# tritag.net
KiCad netlist of a schematic drawn in EAGLE
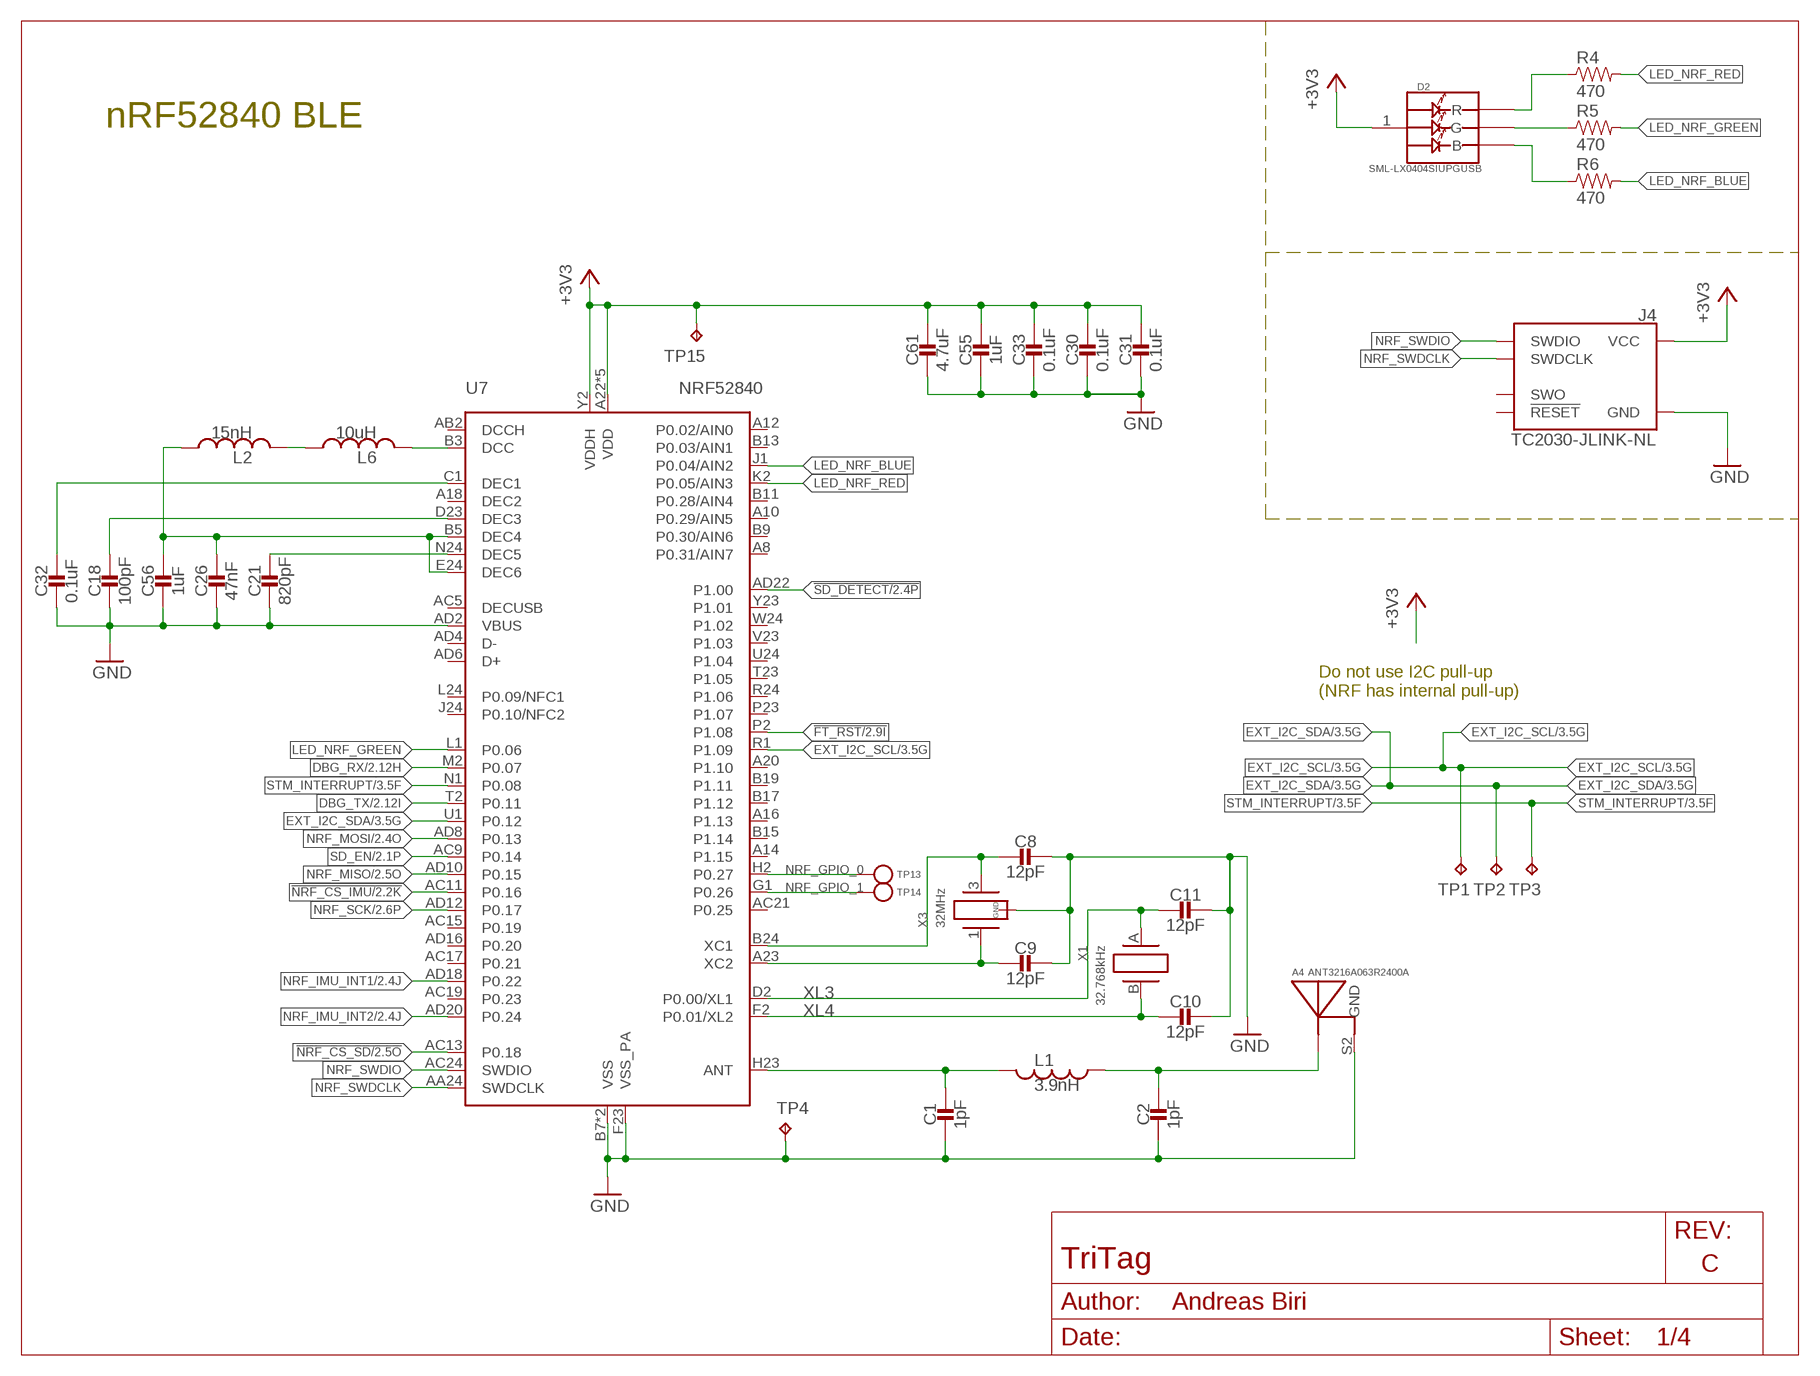
[diagram p0: schematic, sheet 1]
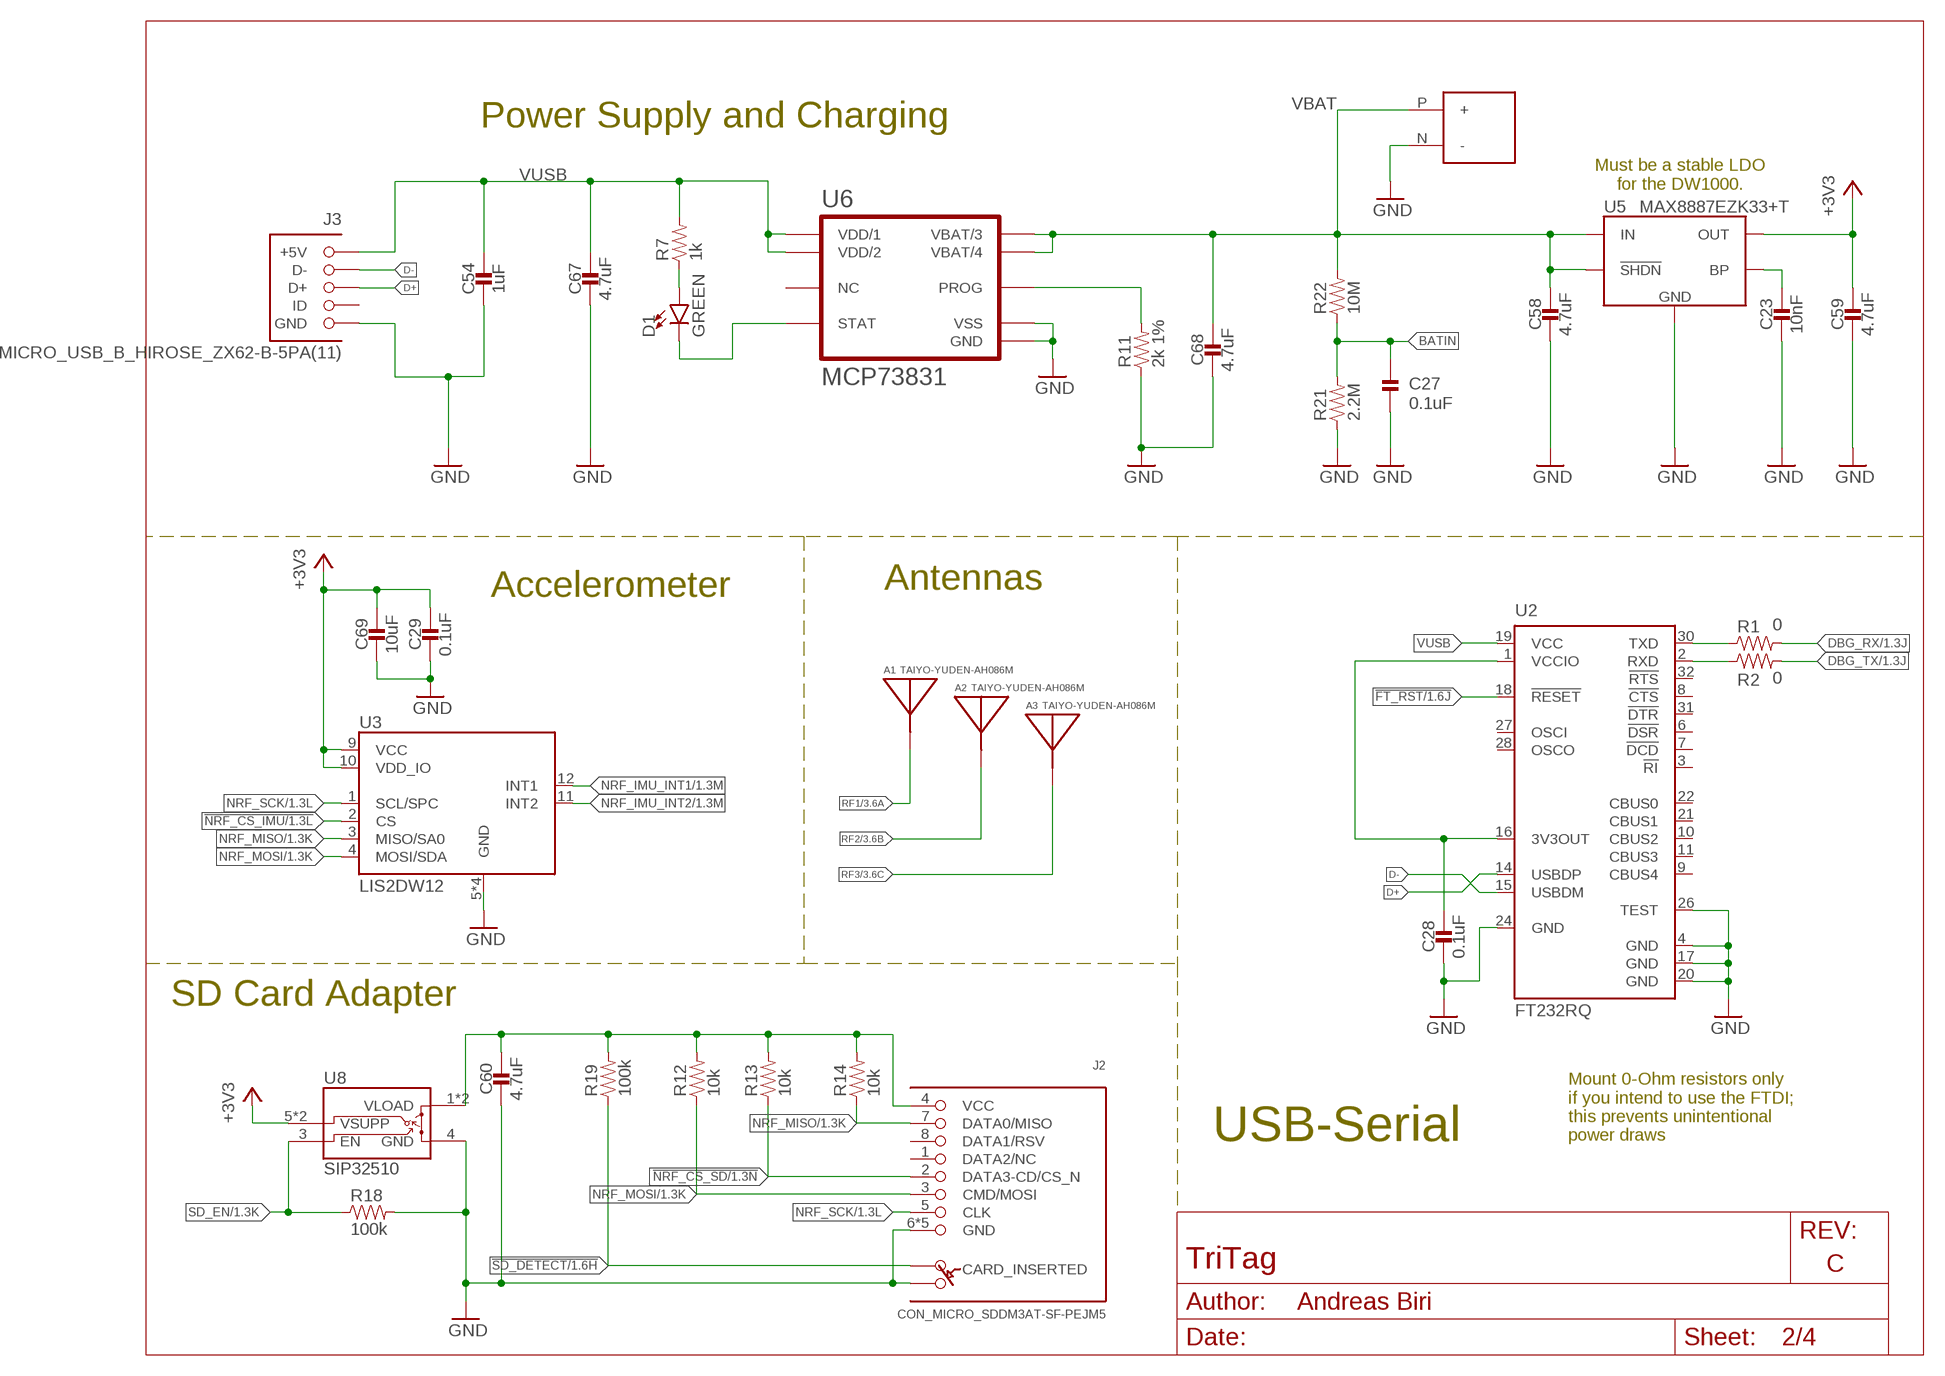
[diagram p1: schematic, sheet 2]
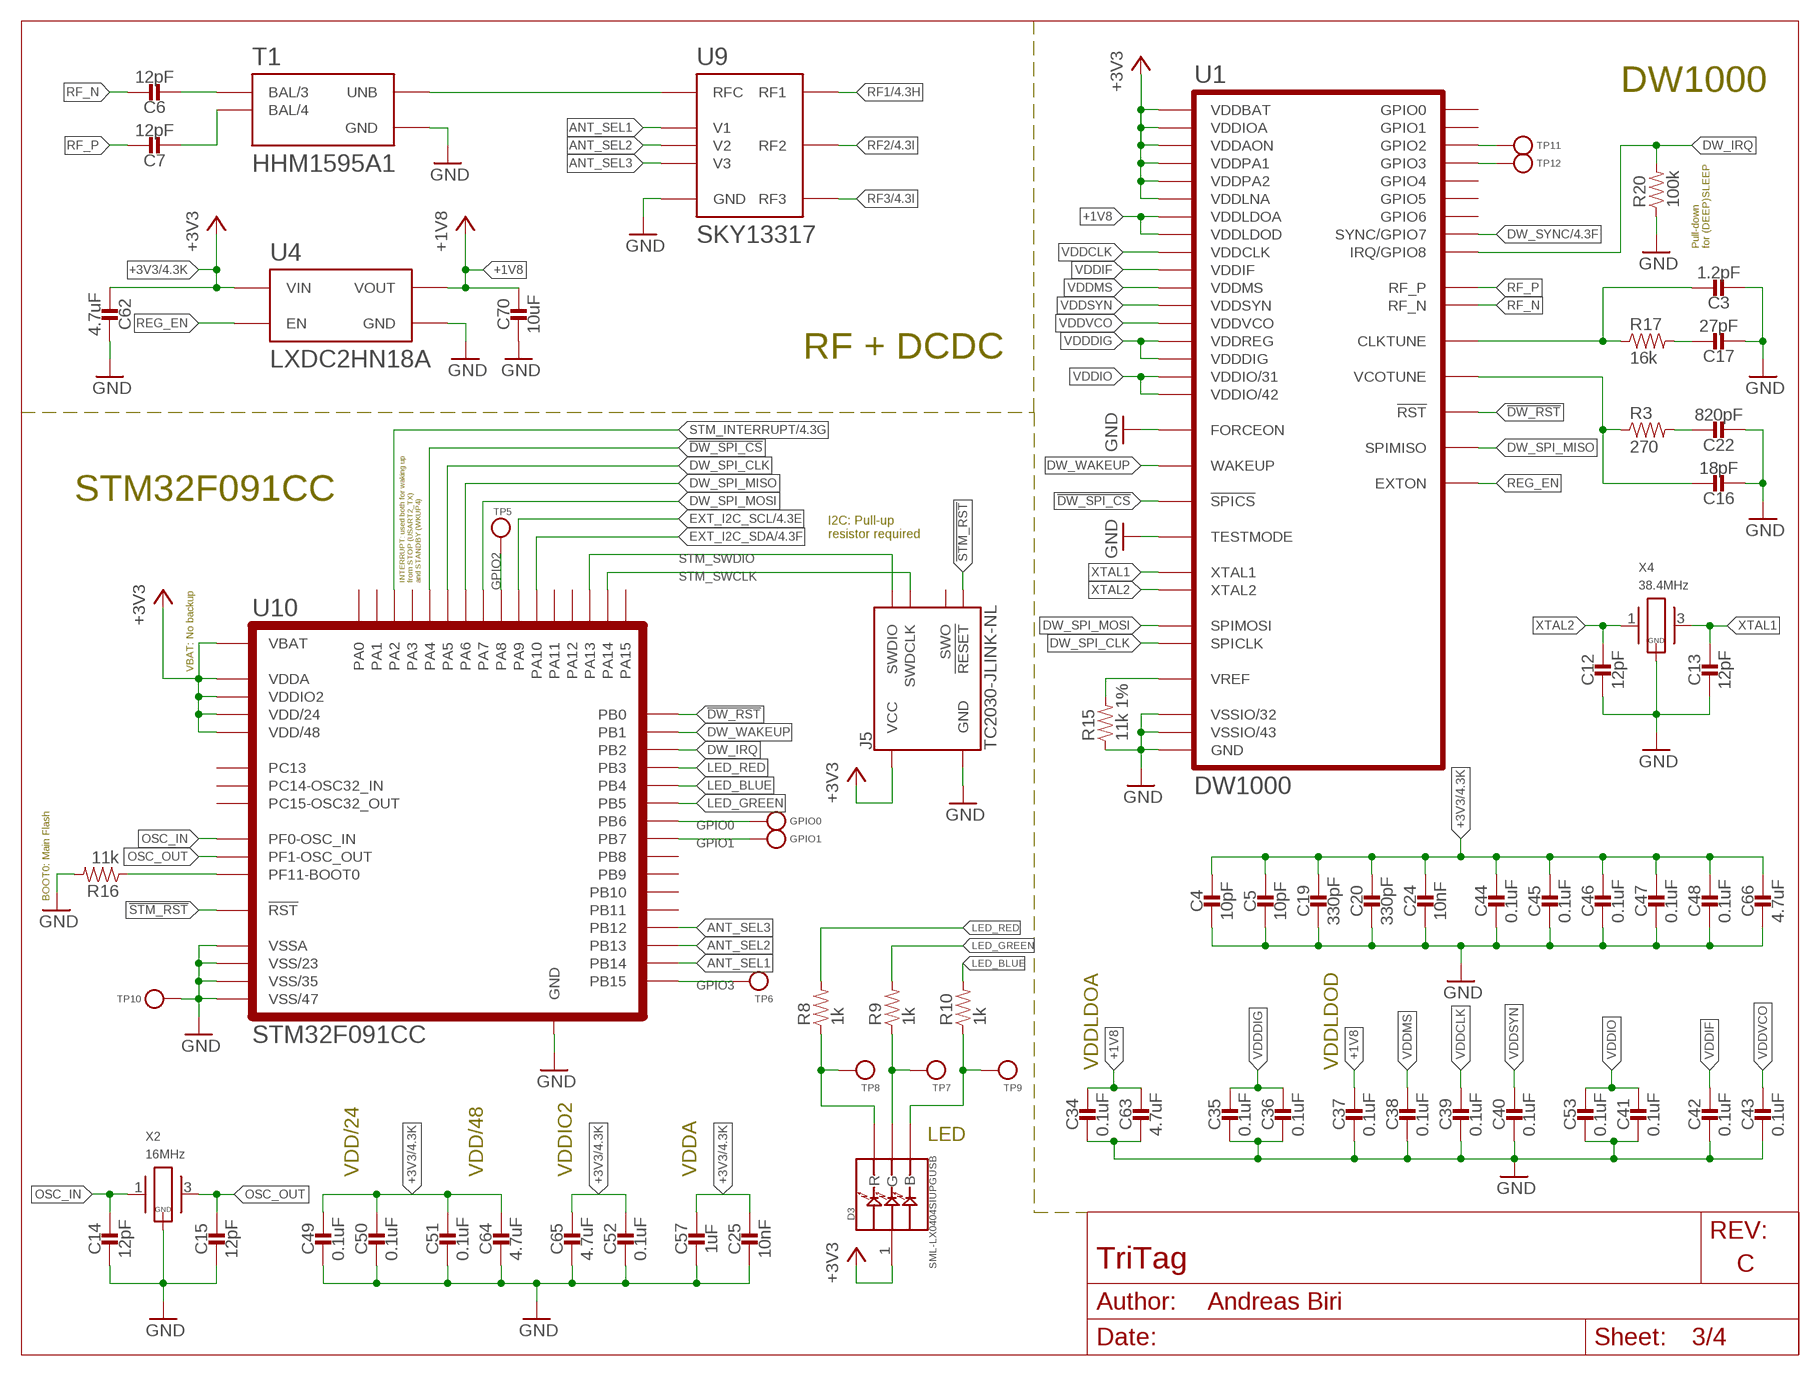
[diagram p2: schematic, sheet 3]
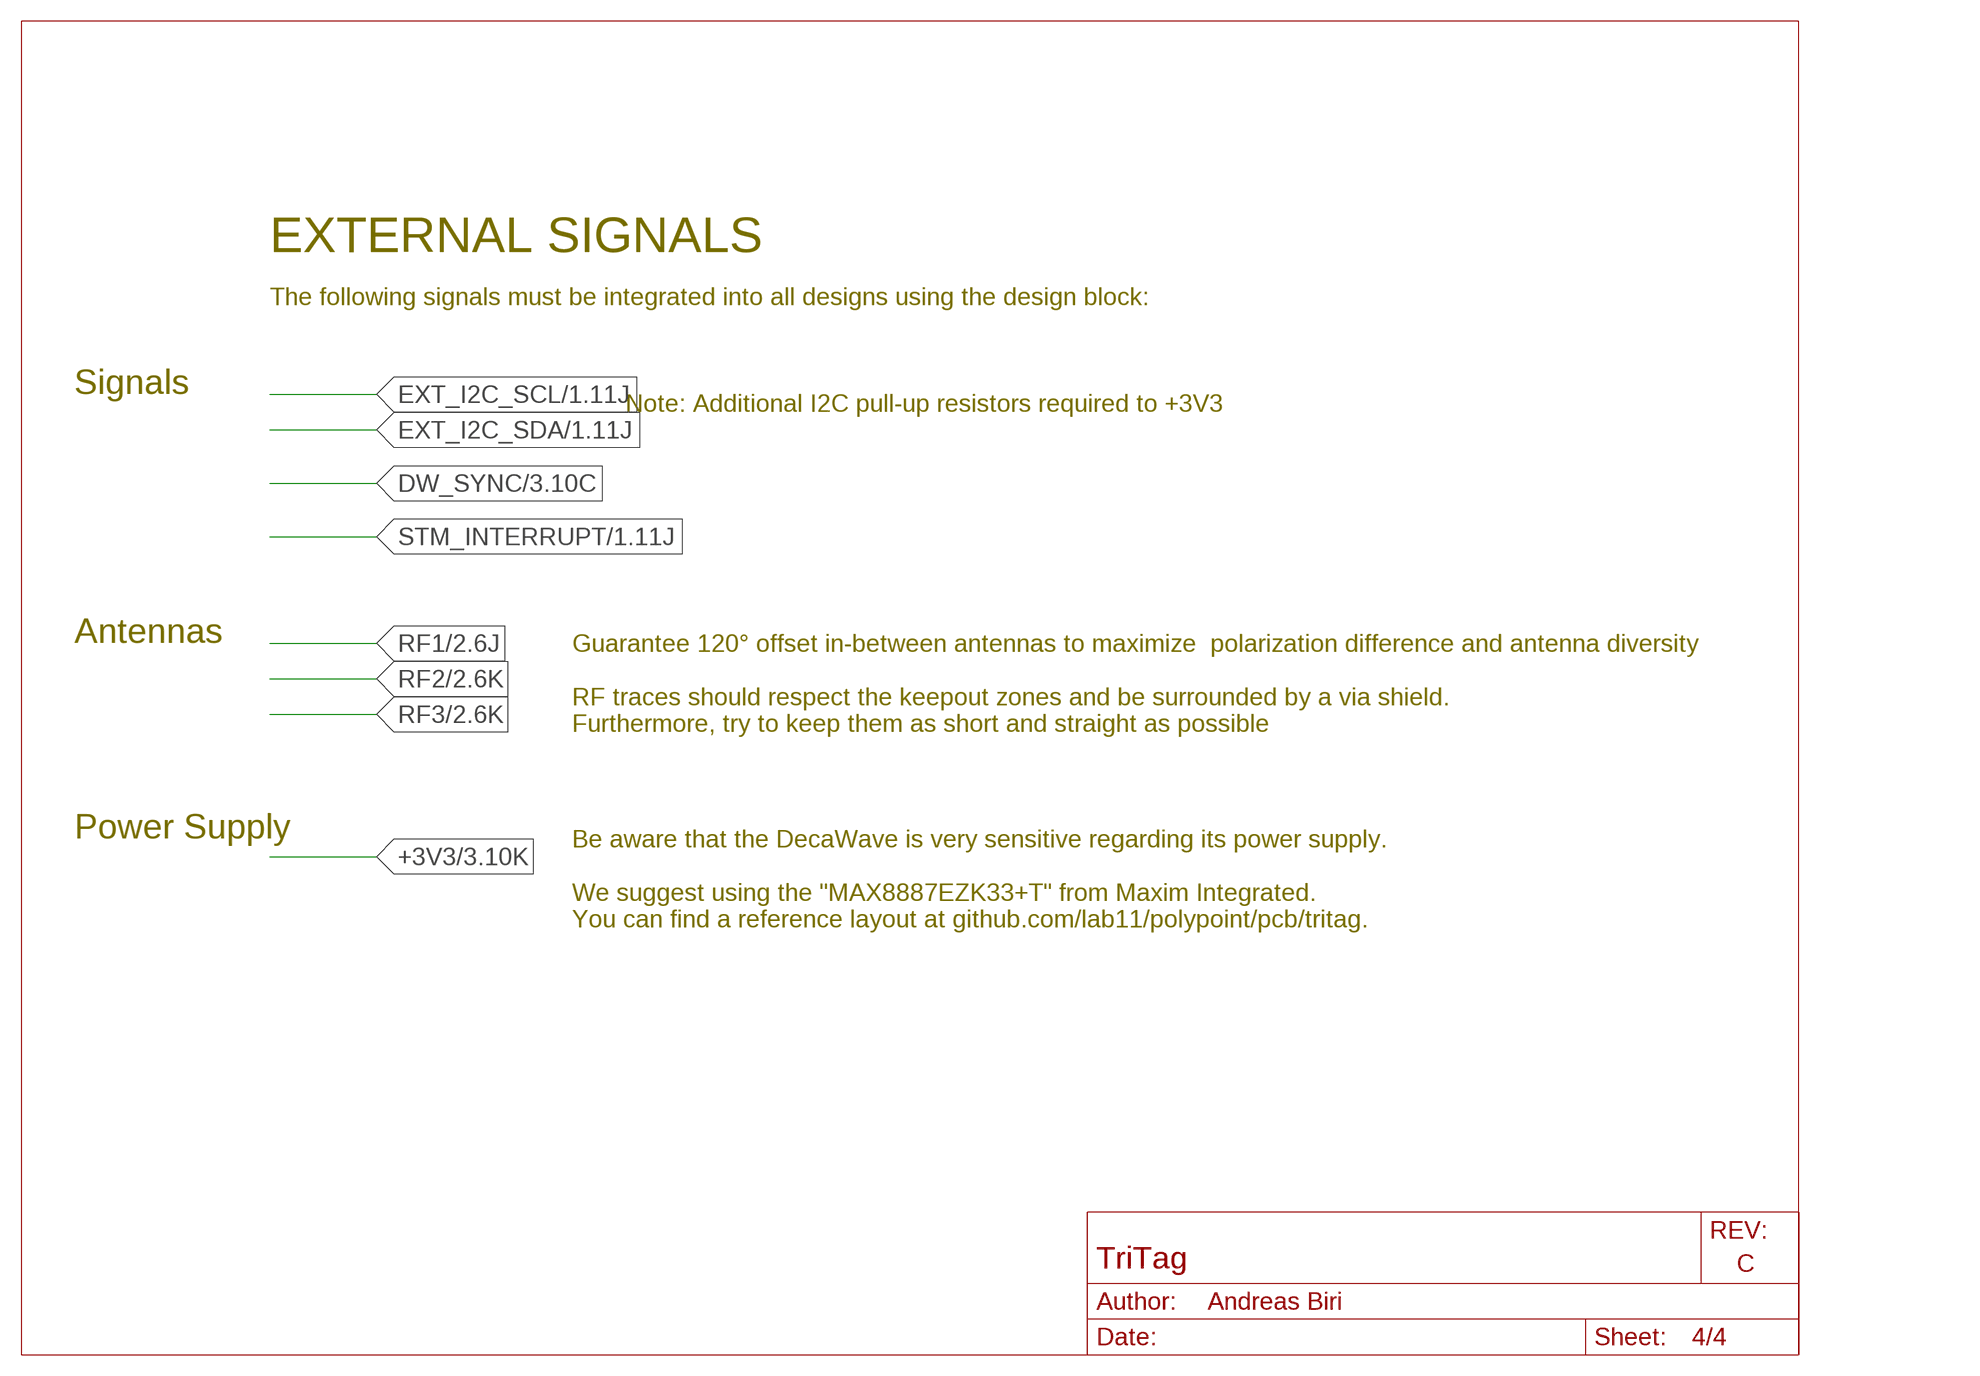
[diagram p3: schematic, sheet 4]

(export (version "E")
  (design (tool "Eeschema 10.0.6"))
  (components
    (comp (ref "A4")
      (value "ANT3216A063R2400A")
      (footprint "eagle-import:ANT3216A063R2400A")
      (fields (field (name "MANUFACTURER") "YAGEO"))
      (libsource (lib "eagle-import") (part "ANT3216A063R2400A"))
    )
    (comp (ref "C1")
      (value "1pF")
      (footprint "eagle-import:0402_CAP")
      (fields (field (name "MPN") "GJM1555C1H1R0CB01D "))
      (libsource (lib "eagle-import") (part "CAPACITOR0402_CAP"))
    )
    (comp (ref "C2")
      (value "1pF")
      (footprint "eagle-import:0402_CAP")
      (fields (field (name "MPN") "GJM1555C1H1R0CB01D"))
      (libsource (lib "eagle-import") (part "CAPACITOR0402_CAP"))
    )
    (comp (ref "C8")
      (value "12pF")
      (footprint "eagle-import:0402_CAP")
      (fields (field (name "MPN") "GRM1555C1H120GA01D "))
      (libsource (lib "eagle-import") (part "CAPACITOR0402_CAP"))
    )
    (comp (ref "C9")
      (value "12pF")
      (footprint "eagle-import:0402_CAP")
      (fields (field (name "MPN") "GRM1555C1H120GA01D "))
      (libsource (lib "eagle-import") (part "CAPACITOR0402_CAP"))
    )
    (comp (ref "C10")
      (value "12pF")
      (footprint "eagle-import:0402_CAP")
      (fields (field (name "MPN") "GRM1555C1H120GA01D "))
      (libsource (lib "eagle-import") (part "CAPACITOR0402_CAP"))
    )
    (comp (ref "C11")
      (value "12pF")
      (footprint "eagle-import:0402_CAP")
      (fields (field (name "MPN") "GRM1555C1H120GA01D "))
      (libsource (lib "eagle-import") (part "CAPACITOR0402_CAP"))
    )
    (comp (ref "C18")
      (value "100pF")
      (footprint "eagle-import:0402_CAP")
      (fields (field (name "MPN") "GRM1555C1H101JA01D "))
      (libsource (lib "eagle-import") (part "CAPACITOR0402_CAP"))
    )
    (comp (ref "C21")
      (value "820pF")
      (footprint "eagle-import:0402_CAP")
      (fields (field (name "MPN") "CL05C821JB5NFNC"))
      (libsource (lib "eagle-import") (part "CAPACITOR0402_CAP"))
    )
    (comp (ref "C26")
      (value "47nF")
      (footprint "eagle-import:0402_CAP")
      (fields (field (name "MPN") "C1005X7R1C473K050BC "))
      (libsource (lib "eagle-import") (part "CAPACITOR0402_CAP"))
    )
    (comp (ref "C30")
      (value "0.1uF")
      (footprint "eagle-import:0402_CAP")
      (fields (field (name "MPN") "GRM155R71C104KA88J "))
      (libsource (lib "eagle-import") (part "CAPACITOR0402_CAP"))
    )
    (comp (ref "C31")
      (value "0.1uF")
      (footprint "eagle-import:0402_CAP")
      (fields (field (name "MPN") "GRM155R71C104KA88J "))
      (libsource (lib "eagle-import") (part "CAPACITOR0402_CAP"))
    )
    (comp (ref "C32")
      (value "0.1uF")
      (footprint "eagle-import:0402_CAP")
      (fields (field (name "MPN") "GRM155R71C104KA88J "))
      (libsource (lib "eagle-import") (part "CAPACITOR0402_CAP"))
    )
    (comp (ref "C33")
      (value "0.1uF")
      (footprint "eagle-import:0402_CAP")
      (fields (field (name "MPN") "GRM155R71C104KA88J "))
      (libsource (lib "eagle-import") (part "CAPACITOR0402_CAP"))
    )
    (comp (ref "C55")
      (value "1uF")
      (footprint "eagle-import:0402_CAP")
      (fields (field (name "MPN") "GRM155R70G105KA12D "))
      (libsource (lib "eagle-import") (part "CAPACITOR0402_CAP"))
    )
    (comp (ref "C56")
      (value "1uF")
      (footprint "eagle-import:0402_CAP")
      (fields (field (name "MPN") "GRM155R70G105KA12D "))
      (libsource (lib "eagle-import") (part "CAPACITOR0402_CAP"))
    )
    (comp (ref "C61")
      (value "4.7uF")
      (footprint "eagle-import:0402_CAP")
      (fields (field (name "MPN") "C1005X5R0J475K050BC "))
      (libsource (lib "eagle-import") (part "CAPACITOR0402_CAP"))
    )
    (comp (ref "D2")
      (value "SML-LX0404SIUPGUSB")
      (footprint "eagle-import:1MM_SQ_4PAD")
      (fields (field (name "MANUFACTURER") "Lumex Opto"))
      (libsource (lib "eagle-import") (part "SML-LX0404SIUPGUSB"))
    )
    (comp (ref "J4")
      (value "TC2030-JLINK-NL")
      (footprint "eagle-import:TC2030-IDC-NL")
      (libsource (lib "eagle-import") (part "TC2030-JLINK-NL"))
    )
    (comp (ref "L1")
      (value "3.9nH")
      (footprint "eagle-import:0402_CAP")
      (fields (field (name "MPN") "AISC-0402-3N9G-T "))
      (libsource (lib "eagle-import") (part "INDUCTOR0402"))
    )
    (comp (ref "L2")
      (value "15nH")
      (footprint "eagle-import:0402_CAP")
      (fields (field (name "MPN") "HK100515NJ-T "))
      (libsource (lib "eagle-import") (part "INDUCTOR0402"))
    )
    (comp (ref "L6")
      (value "10uH")
      (footprint "eagle-import:0603_CAP")
      (fields (field (name "MPN") "LQM18FN100M00D "))
      (libsource (lib "eagle-import") (part "INDUCTOR0603"))
    )
    (comp (ref "R4")
      (value "470")
      (footprint "eagle-import:0402_RES")
      (libsource (lib "eagle-import") (part "RESISTOR0402_RES"))
    )
    (comp (ref "R5")
      (value "470")
      (footprint "eagle-import:0402_RES")
      (libsource (lib "eagle-import") (part "RESISTOR0402_RES"))
    )
    (comp (ref "R6")
      (value "470")
      (footprint "eagle-import:0402_RES")
      (libsource (lib "eagle-import") (part "RESISTOR0402_RES"))
    )
    (comp (ref "TP1")
      (value "TPTP06SQ")
      (footprint "eagle-import:TP06SQ")
      (libsource (lib "eagle-import") (part "TPTP06SQ"))
    )
    (comp (ref "TP2")
      (value "TPTP06SQ")
      (footprint "eagle-import:TP06SQ")
      (libsource (lib "eagle-import") (part "TPTP06SQ"))
    )
    (comp (ref "TP3")
      (value "TPTP06SQ")
      (footprint "eagle-import:TP06SQ")
      (libsource (lib "eagle-import") (part "TPTP06SQ"))
    )
    (comp (ref "TP4")
      (value "TPTP06SQ")
      (footprint "eagle-import:TP06SQ")
      (libsource (lib "eagle-import") (part "TPTP06SQ"))
    )
    (comp (ref "TP13")
      (value "TEST-POINT")
      (footprint "eagle-import:PAD.03X.03")
      (libsource (lib "eagle-import") (part "TEST-POINT"))
    )
    (comp (ref "TP14")
      (value "TEST-POINT")
      (footprint "eagle-import:PAD.03X.03")
      (libsource (lib "eagle-import") (part "TEST-POINT"))
    )
    (comp (ref "TP15")
      (value "TPTP06SQ")
      (footprint "eagle-import:TP06SQ")
      (libsource (lib "eagle-import") (part "TPTP06SQ"))
    )
    (comp (ref "U7")
      (value "NRF52840")
      (footprint "eagle-import:AQFN73")
      (fields (field (name "MANUFACTURER") "NORIDIC SEMICONDUCTOR"))
      (libsource (lib "eagle-import") (part "NRF52840"))
    )
    (comp (ref "X1")
      (value "32.768kHz")
      (footprint "eagle-import:ABS05")
      (fields (field (name "MANUFACTURER") "Abracon") (field (name "MPN") "ABS05-32.768KHZ-9-T"))
      (libsource (lib "eagle-import") (part "ABS05-32.768KHZ-9-T"))
    )
    (comp (ref "X3")
      (value "32MHz")
      (footprint "eagle-import:TXC-7V")
      (fields (field (name "MANUFACTURER") "TXC CORPORATION") (field (name "MPN") "7M-32.000MAHV-T"))
      (libsource (lib "eagle-import") (part "7V-32.000MAHV-T"))
    )
    (comp (ref "C3")
      (value "1.2pF")
      (footprint "eagle-import:0402_CAP")
      (libsource (lib "eagle-import") (part "CAPACITOR0402_CAP"))
    )
    (comp (ref "C4")
      (value "10pF")
      (footprint "eagle-import:0402_CAP")
      (libsource (lib "eagle-import") (part "CAPACITOR0402_CAP"))
    )
    (comp (ref "C5")
      (value "10pF")
      (footprint "eagle-import:0402_CAP")
      (libsource (lib "eagle-import") (part "CAPACITOR0402_CAP"))
    )
    (comp (ref "C6")
      (value "12pF")
      (footprint "eagle-import:0201_CAP")
      (libsource (lib "eagle-import") (part "CAPACITOR0201_CAP"))
    )
    (comp (ref "C7")
      (value "12pF")
      (footprint "eagle-import:0201_CAP")
      (libsource (lib "eagle-import") (part "CAPACITOR0201_CAP"))
    )
    (comp (ref "C12")
      (value "12pF")
      (footprint "eagle-import:0402_CAP")
      (libsource (lib "eagle-import") (part "CAPACITOR0402_CAP"))
    )
    (comp (ref "C13")
      (value "12pF")
      (footprint "eagle-import:0402_CAP")
      (libsource (lib "eagle-import") (part "CAPACITOR0402_CAP"))
    )
    (comp (ref "C14")
      (value "12pF")
      (footprint "eagle-import:0402_CAP")
      (libsource (lib "eagle-import") (part "CAPACITOR0402_CAP"))
    )
    (comp (ref "C15")
      (value "12pF")
      (footprint "eagle-import:0402_CAP")
      (libsource (lib "eagle-import") (part "CAPACITOR0402_CAP"))
    )
    (comp (ref "C16")
      (value "18pF")
      (footprint "eagle-import:0402_CAP")
      (libsource (lib "eagle-import") (part "CAPACITOR0402_CAP"))
    )
    (comp (ref "C17")
      (value "27pF")
      (footprint "eagle-import:0402_CAP")
      (libsource (lib "eagle-import") (part "CAPACITOR0402_CAP"))
    )
    (comp (ref "C19")
      (value "330pF")
      (footprint "eagle-import:0402_CAP")
      (libsource (lib "eagle-import") (part "CAPACITOR0402_CAP"))
    )
    (comp (ref "C20")
      (value "330pF")
      (footprint "eagle-import:0402_CAP")
      (libsource (lib "eagle-import") (part "CAPACITOR0402_CAP"))
    )
    (comp (ref "C22")
      (value "820pF")
      (footprint "eagle-import:0402_CAP")
      (libsource (lib "eagle-import") (part "CAPACITOR0402_CAP"))
    )
    (comp (ref "C24")
      (value "10nF")
      (footprint "eagle-import:0402_CAP")
      (libsource (lib "eagle-import") (part "CAPACITOR0402_CAP"))
    )
    (comp (ref "C25")
      (value "10nF")
      (footprint "eagle-import:0402_CAP")
      (libsource (lib "eagle-import") (part "CAPACITOR0402_CAP"))
    )
    (comp (ref "C34")
      (value "0.1uF")
      (footprint "eagle-import:0402_CAP")
      (libsource (lib "eagle-import") (part "CAPACITOR0402_CAP"))
    )
    (comp (ref "C35")
      (value "0.1uF")
      (footprint "eagle-import:0402_CAP")
      (libsource (lib "eagle-import") (part "CAPACITOR0402_CAP"))
    )
    (comp (ref "C36")
      (value "0.1uF")
      (footprint "eagle-import:0402_CAP")
      (libsource (lib "eagle-import") (part "CAPACITOR0402_CAP"))
    )
    (comp (ref "C37")
      (value "0.1uF")
      (footprint "eagle-import:0402_CAP")
      (libsource (lib "eagle-import") (part "CAPACITOR0402_CAP"))
    )
    (comp (ref "C38")
      (value "0.1uF")
      (footprint "eagle-import:0402_CAP")
      (libsource (lib "eagle-import") (part "CAPACITOR0402_CAP"))
    )
    (comp (ref "C39")
      (value "0.1uF")
      (footprint "eagle-import:0402_CAP")
      (libsource (lib "eagle-import") (part "CAPACITOR0402_CAP"))
    )
    (comp (ref "C40")
      (value "0.1uF")
      (footprint "eagle-import:0402_CAP")
      (libsource (lib "eagle-import") (part "CAPACITOR0402_CAP"))
    )
    (comp (ref "C41")
      (value "0.1uF")
      (footprint "eagle-import:0402_CAP")
      (libsource (lib "eagle-import") (part "CAPACITOR0402_CAP"))
    )
    (comp (ref "C42")
      (value "0.1uF")
      (footprint "eagle-import:0402_CAP")
      (libsource (lib "eagle-import") (part "CAPACITOR0402_CAP"))
    )
    (comp (ref "C43")
      (value "0.1uF")
      (footprint "eagle-import:0402_CAP")
      (libsource (lib "eagle-import") (part "CAPACITOR0402_CAP"))
    )
    (comp (ref "C44")
      (value "0.1uF")
      (footprint "eagle-import:0402_CAP")
      (libsource (lib "eagle-import") (part "CAPACITOR0402_CAP"))
    )
    (comp (ref "C45")
      (value "0.1uF")
      (footprint "eagle-import:0402_CAP")
      (libsource (lib "eagle-import") (part "CAPACITOR0402_CAP"))
    )
    (comp (ref "C46")
      (value "0.1uF")
      (footprint "eagle-import:0402_CAP")
      (libsource (lib "eagle-import") (part "CAPACITOR0402_CAP"))
    )
    (comp (ref "C47")
      (value "0.1uF")
      (footprint "eagle-import:0402_CAP")
      (libsource (lib "eagle-import") (part "CAPACITOR0402_CAP"))
    )
    (comp (ref "C48")
      (value "0.1uF")
      (footprint "eagle-import:0402_CAP")
      (libsource (lib "eagle-import") (part "CAPACITOR0402_CAP"))
    )
    (comp (ref "C49")
      (value "0.1uF")
      (footprint "eagle-import:0402_CAP")
      (libsource (lib "eagle-import") (part "CAPACITOR0402_CAP"))
    )
    (comp (ref "C50")
      (value "0.1uF")
      (footprint "eagle-import:0402_CAP")
      (libsource (lib "eagle-import") (part "CAPACITOR0402_CAP"))
    )
    (comp (ref "C51")
      (value "0.1uF")
      (footprint "eagle-import:0402_CAP")
      (libsource (lib "eagle-import") (part "CAPACITOR0402_CAP"))
    )
    (comp (ref "C52")
      (value "0.1uF")
      (footprint "eagle-import:0402_CAP")
      (libsource (lib "eagle-import") (part "CAPACITOR0402_CAP"))
    )
    (comp (ref "C53")
      (value "0.1uF")
      (footprint "eagle-import:0402_CAP")
      (libsource (lib "eagle-import") (part "CAPACITOR0402_CAP"))
    )
    (comp (ref "C57")
      (value "1uF")
      (footprint "eagle-import:0402_CAP")
      (libsource (lib "eagle-import") (part "CAPACITOR0402_CAP"))
    )
    (comp (ref "C62")
      (value "4.7uF")
      (footprint "eagle-import:0402_CAP")
      (libsource (lib "eagle-import") (part "CAPACITOR0402_CAP"))
    )
    (comp (ref "C63")
      (value "4.7uF")
      (footprint "eagle-import:0402_CAP")
      (libsource (lib "eagle-import") (part "CAPACITOR0402_CAP"))
    )
    (comp (ref "C64")
      (value "4.7uF")
      (footprint "eagle-import:0402_CAP")
      (libsource (lib "eagle-import") (part "CAPACITOR0402_CAP"))
    )
    (comp (ref "C65")
      (value "4.7uF")
      (footprint "eagle-import:0402_CAP")
      (libsource (lib "eagle-import") (part "CAPACITOR0402_CAP"))
    )
    (comp (ref "C66")
      (value "4.7uF")
      (footprint "eagle-import:0402_CAP")
      (libsource (lib "eagle-import") (part "CAPACITOR0402_CAP"))
    )
    (comp (ref "C70")
      (value "10uF")
      (footprint "eagle-import:0603_CAP")
      (libsource (lib "eagle-import") (part "CAPACITOR0603_CAP"))
    )
    (comp (ref "D3")
      (value "SML-LX0404SIUPGUSB")
      (footprint "eagle-import:1MM_SQ_4PAD")
      (fields (field (name "MANUFACTURER") "Lumex Opto"))
      (libsource (lib "eagle-import") (part "SML-LX0404SIUPGUSB"))
    )
    (comp (ref "GPIO0")
      (value "TEST-POINT")
      (footprint "eagle-import:PAD.03X.03")
      (libsource (lib "eagle-import") (part "TEST-POINT"))
    )
    (comp (ref "GPIO1")
      (value "TEST-POINT")
      (footprint "eagle-import:PAD.03X.03")
      (libsource (lib "eagle-import") (part "TEST-POINT"))
    )
    (comp (ref "J5")
      (value "TC2030-JLINK-NL")
      (footprint "eagle-import:TC2030-IDC-NL")
      (libsource (lib "eagle-import") (part "TC2030-JLINK-NL"))
    )
    (comp (ref "R3")
      (value "270")
      (footprint "eagle-import:0402_RES")
      (libsource (lib "eagle-import") (part "RESISTOR0402_RES"))
    )
    (comp (ref "R8")
      (value "1k")
      (footprint "eagle-import:0402_RES")
      (libsource (lib "eagle-import") (part "RESISTOR0402_RES"))
    )
    (comp (ref "R9")
      (value "1k")
      (footprint "eagle-import:0402_RES")
      (libsource (lib "eagle-import") (part "RESISTOR0402_RES"))
    )
    (comp (ref "R10")
      (value "1k")
      (footprint "eagle-import:0402_RES")
      (libsource (lib "eagle-import") (part "RESISTOR0402_RES"))
    )
    (comp (ref "R15")
      (value "11k 1%")
      (footprint "eagle-import:0402_RES")
      (libsource (lib "eagle-import") (part "RESISTOR0402_RES"))
    )
    (comp (ref "R16")
      (value "11k")
      (footprint "eagle-import:0402_RES")
      (libsource (lib "eagle-import") (part "RESISTOR0402_RES"))
    )
    (comp (ref "R17")
      (value "16k")
      (footprint "eagle-import:0402_RES")
      (libsource (lib "eagle-import") (part "RESISTOR0402_RES"))
    )
    (comp (ref "R20")
      (value "100k")
      (footprint "eagle-import:0402_RES")
      (libsource (lib "eagle-import") (part "RESISTOR0402_RES"))
    )
    (comp (ref "T1")
      (value "HHM1595A1")
      (footprint "eagle-import:EIA-0805")
      (fields (field (name "MANUFACTURER") "TDK Corporation"))
      (libsource (lib "eagle-import") (part "HHM1595A1"))
    )
    (comp (ref "TP5")
      (value "TEST-POINT")
      (footprint "eagle-import:PAD.03X.03")
      (libsource (lib "eagle-import") (part "TEST-POINT"))
    )
    (comp (ref "TP6")
      (value "TEST-POINT")
      (footprint "eagle-import:PAD.03X.03")
      (libsource (lib "eagle-import") (part "TEST-POINT"))
    )
    (comp (ref "TP7")
      (value "TEST-POINT")
      (footprint "eagle-import:PAD.03X.03")
      (libsource (lib "eagle-import") (part "TEST-POINT"))
    )
    (comp (ref "TP8")
      (value "TEST-POINT")
      (footprint "eagle-import:PAD.03X.03")
      (libsource (lib "eagle-import") (part "TEST-POINT"))
    )
    (comp (ref "TP9")
      (value "TEST-POINT")
      (footprint "eagle-import:PAD.03X.03")
      (libsource (lib "eagle-import") (part "TEST-POINT"))
    )
    (comp (ref "TP10")
      (value "TEST-POINT")
      (footprint "eagle-import:PAD.03X.03")
      (libsource (lib "eagle-import") (part "TEST-POINT"))
    )
    (comp (ref "TP11")
      (value "TEST-POINT")
      (footprint "eagle-import:PAD.03X.03")
      (libsource (lib "eagle-import") (part "TEST-POINT"))
    )
    (comp (ref "TP12")
      (value "TEST-POINT")
      (footprint "eagle-import:PAD.03X.03")
      (libsource (lib "eagle-import") (part "TEST-POINT"))
    )
    (comp (ref "U1")
      (value "DW1000")
      (footprint "eagle-import:QFN-48-DW1000")
      (fields (field (name "MANUFACTURER") "Decawave Limited") (field (name "MPN") "DW1000-I-TR13"))
      (libsource (lib "eagle-import") (part "DW1000"))
    )
    (comp (ref "U4")
      (value "LXDC2HN18A")
      (footprint "eagle-import:LXDC2HN")
      (fields
        (field (name "MANUFACTURER") "Murata Electronics North America")
        (field (name "MPN") "LXDC2HN18A-097")
      )
      (libsource (lib "eagle-import") (part "LXDC2HN18A"))
    )
    (comp (ref "U9")
      (value "SKY13317")
      (footprint "eagle-import:MLPQ-UT-8")
      (fields (field (name "MANUFACTURER") "Skyworks Solutions Inc.") (field (name "MPN") "SKY13317-373LF"))
      (libsource (lib "eagle-import") (part "SKY13317"))
    )
    (comp (ref "U10")
      (value "STM32F091CC")
      (footprint "eagle-import:UFQFPN-48")
      (fields (field (name "MANUFACTURER") "STMicroelectronics") (field (name "MPN") "STM32F091CCU6"))
      (libsource (lib "eagle-import") (part "STM32F091CC"))
    )
    (comp (ref "X2")
      (value "16MHz")
      (footprint "eagle-import:FA-20H")
      (description "16MHz ±10ppm Crystal 8pF 80 Ohms 4-SMD, No Lead")
      (fields (field (name "MANUFACTURER") "EPSON"))
      (libsource (lib "eagle-import") (part "FA-20H"))
    )
    (comp (ref "X4")
      (value "38.4MHz")
      (footprint "eagle-import:FA-20H")
      (description "38.4MHz ±10ppm Crystal 8.5pF 40 Ohms 4-SMD, No Lead")
      (fields (field (name "MANUFACTURER") "EPSON"))
      (libsource (lib "eagle-import") (part "FA-20H"))
    )
    (comp (ref "A1")
      (value "TAIYO-YUDEN-AH086M")
      (footprint "eagle-import:TAIYO-YUDEN-AH086M")
      (libsource (lib "eagle-import") (part "TAIYO-YUDEN-AH086M"))
    )
    (comp (ref "A2")
      (value "TAIYO-YUDEN-AH086M")
      (footprint "eagle-import:TAIYO-YUDEN-AH086M")
      (libsource (lib "eagle-import") (part "TAIYO-YUDEN-AH086M"))
    )
    (comp (ref "A3")
      (value "TAIYO-YUDEN-AH086M")
      (footprint "eagle-import:TAIYO-YUDEN-AH086M")
      (libsource (lib "eagle-import") (part "TAIYO-YUDEN-AH086M"))
    )
    (comp (ref "C23")
      (value "10nF")
      (footprint "eagle-import:0402_CAP")
      (libsource (lib "eagle-import") (part "CAPACITOR0402_CAP"))
    )
    (comp (ref "C27")
      (value "0.1uF")
      (footprint "eagle-import:0402_CAP")
      (libsource (lib "eagle-import") (part "CAPACITOR0402_CAP"))
    )
    (comp (ref "C28")
      (value "0.1uF")
      (footprint "eagle-import:0402_CAP")
      (fields (field (name "MPN") "GRM155R71C104KA88J "))
      (libsource (lib "eagle-import") (part "CAPACITOR0402_CAP"))
    )
    (comp (ref "C29")
      (value "0.1uF")
      (footprint "eagle-import:0402_CAP")
      (fields (field (name "MPN") "GRM155R71C104KA88J "))
      (libsource (lib "eagle-import") (part "CAPACITOR0402_CAP"))
    )
    (comp (ref "C54")
      (value "1uF")
      (footprint "eagle-import:0402_CAP")
      (libsource (lib "eagle-import") (part "CAPACITOR0402_CAP"))
    )
    (comp (ref "C58")
      (value "4.7uF")
      (footprint "eagle-import:0402_CAP")
      (libsource (lib "eagle-import") (part "CAPACITOR0402_CAP"))
    )
    (comp (ref "C59")
      (value "4.7uF")
      (footprint "eagle-import:0402_CAP")
      (libsource (lib "eagle-import") (part "CAPACITOR0402_CAP"))
    )
    (comp (ref "C60")
      (value "4.7uF")
      (footprint "eagle-import:0402_CAP")
      (description "CAP CER 4.7UF 6.3V X5R 0402")
      (fields (field (name "MANUFACTURER") "TDK") (field (name "MPN") "C1005X5R0J475K050BC"))
      (libsource (lib "eagle-import") (part "CAPACITOR0402_CAP"))
    )
    (comp (ref "C67")
      (value "4.7uF")
      (footprint "eagle-import:0402_CAP")
      (libsource (lib "eagle-import") (part "CAPACITOR0402_CAP"))
    )
    (comp (ref "C68")
      (value "4.7uF")
      (footprint "eagle-import:0402_CAP")
      (libsource (lib "eagle-import") (part "CAPACITOR0402_CAP"))
    )
    (comp (ref "C69")
      (value "10uF")
      (footprint "eagle-import:0603_CAP")
      (fields (field (name "MPN") "GRM188R60J106ME47D "))
      (libsource (lib "eagle-import") (part "CAPACITOR0603_CAP"))
    )
    (comp (ref "D1")
      (value "GREEN")
      (footprint "eagle-import:LED-0603")
      (libsource (lib "eagle-import") (part "LED0603"))
    )
    (comp (ref "J1")
      (value "BAT_HOLE")
      (footprint "eagle-import:BATTERY_HOLE")
      (libsource (lib "eagle-import") (part "BAT_HOLE"))
    )
    (comp (ref "J2")
      (value "CON_MICRO_SDDM3AT-SF-PEJM5")
      (footprint "eagle-import:DM3AT-SF-PEJM5")
      (libsource (lib "eagle-import") (part "CON_MICRO_SDDM3AT-SF-PEJM5"))
    )
    (comp (ref "J3")
      (value "MICRO_USB_B_HIROSE_ZX62-B-5PA(11)")
      (footprint "eagle-import:USB_MICRO_B-HIROSE-ZX62-B-5PA(11)")
      (libsource (lib "eagle-import") (part "MICRO_USB_B_HIROSE_ZX62-B-5PA(11)"))
    )
    (comp (ref "R1")
      (value "0")
      (footprint "eagle-import:0402_RES")
      (libsource (lib "eagle-import") (part "RESISTOR0402_RES"))
    )
    (comp (ref "R2")
      (value "0")
      (footprint "eagle-import:0402_RES")
      (libsource (lib "eagle-import") (part "RESISTOR0402_RES"))
    )
    (comp (ref "R7")
      (value "1k")
      (footprint "eagle-import:0402_RES")
      (libsource (lib "eagle-import") (part "RESISTOR0402_RES"))
    )
    (comp (ref "R11")
      (value "2k 1%")
      (footprint "eagle-import:0402_RES")
      (libsource (lib "eagle-import") (part "RESISTOR0402_RES"))
    )
    (comp (ref "R12")
      (value "10k")
      (footprint "eagle-import:0402_RES")
      (libsource (lib "eagle-import") (part "RESISTOR0402_RES"))
    )
    (comp (ref "R13")
      (value "10k")
      (footprint "eagle-import:0402_RES")
      (libsource (lib "eagle-import") (part "RESISTOR0402_RES"))
    )
    (comp (ref "R14")
      (value "10k")
      (footprint "eagle-import:0402_RES")
      (libsource (lib "eagle-import") (part "RESISTOR0402_RES"))
    )
    (comp (ref "R18")
      (value "100k")
      (footprint "eagle-import:0402_RES")
      (libsource (lib "eagle-import") (part "RESISTOR0402_RES"))
    )
    (comp (ref "R19")
      (value "100k")
      (footprint "eagle-import:0402_RES")
      (libsource (lib "eagle-import") (part "RESISTOR0402_RES"))
    )
    (comp (ref "R21")
      (value "2.2M")
      (footprint "eagle-import:0402_RES")
      (libsource (lib "eagle-import") (part "RESISTOR0402_RES"))
    )
    (comp (ref "R22")
      (value "10M")
      (footprint "eagle-import:0402_RES")
      (libsource (lib "eagle-import") (part "RESISTOR0402_RES"))
    )
    (comp (ref "U2")
      (value "FT232RQ")
      (footprint "eagle-import:QFN32")
      (libsource (lib "eagle-import") (part "FT232RQ"))
    )
    (comp (ref "U3")
      (value "LIS2DW12")
      (footprint "eagle-import:LGA-12")
      (fields (field (name "MANUFACTURER") "STMicroelectronics") (field (name "MPN") "LIS2DW12TR"))
      (libsource (lib "eagle-import") (part "LIS2DW12"))
    )
    (comp (ref "U5")
      (value "MAX8887EZK33+T")
      (footprint "eagle-import:SOT-23-5")
      (libsource (lib "eagle-import") (part "MAX8887EZK33+T"))
    )
    (comp (ref "U6")
      (value "MCP73831")
      (footprint "eagle-import:DFN-8-MCP")
      (fields (field (name "MANUFACTURER") "Microchip Technology") (field (name "MPN") "MCP73831T-2ACI/MC"))
      (libsource (lib "eagle-import") (part "MCP73831"))
    )
    (comp (ref "U8")
      (value "SIP32510")
      (footprint "eagle-import:TSOT23-6")
      (fields (field (name "MANUFACTURER") "Vishay") (field (name "MPN") "SIP32510DT-T1-GE3"))
      (libsource (lib "eagle-import") (part "SIP32510"))
    )
  )
  (nets
    (net (code "1") (name "+1V8") (class "Default")
      (node (ref "C34") (pin "1") (pinfunction "1_1") (pintype "bidirectional"))
      (node (ref "C37") (pin "1") (pinfunction "1_1") (pintype "bidirectional"))
      (node (ref "C63") (pin "1") (pinfunction "1_1") (pintype "bidirectional"))
      (node (ref "C70") (pin "1") (pinfunction "1_1") (pintype "bidirectional"))
      (node (ref "U1") (pin "26") (pinfunction "VDDLDOD_26") (pintype "power_in"))
      (node (ref "U1") (pin "48") (pinfunction "VDDLDOA_48") (pintype "power_in"))
      (node (ref "U4") (pin "3") (pinfunction "VOUT_3") (pintype "power_in"))
    )
    (net (code "2") (name "+3V3") (class "Default")
      (node (ref "C19") (pin "1") (pinfunction "1_1") (pintype "bidirectional"))
      (node (ref "C20") (pin "1") (pinfunction "1_1") (pintype "bidirectional"))
      (node (ref "C24") (pin "1") (pinfunction "1_1") (pintype "bidirectional"))
      (node (ref "C25") (pin "1") (pinfunction "1_1") (pintype "bidirectional"))
      (node (ref "C29") (pin "1") (pinfunction "1_1") (pintype "bidirectional"))
      (node (ref "C30") (pin "1") (pinfunction "1_1") (pintype "bidirectional"))
      (node (ref "C31") (pin "1") (pinfunction "1_1") (pintype "bidirectional"))
      (node (ref "C33") (pin "1") (pinfunction "1_1") (pintype "bidirectional"))
      (node (ref "C4") (pin "1") (pinfunction "1_1") (pintype "bidirectional"))
      (node (ref "C44") (pin "1") (pinfunction "1_1") (pintype "bidirectional"))
      (node (ref "C45") (pin "1") (pinfunction "1_1") (pintype "bidirectional"))
      (node (ref "C46") (pin "1") (pinfunction "1_1") (pintype "bidirectional"))
      (node (ref "C47") (pin "1") (pinfunction "1_1") (pintype "bidirectional"))
      (node (ref "C48") (pin "1") (pinfunction "1_1") (pintype "bidirectional"))
      (node (ref "C49") (pin "1") (pinfunction "1_1") (pintype "bidirectional"))
      (node (ref "C5") (pin "1") (pinfunction "1_1") (pintype "bidirectional"))
      (node (ref "C50") (pin "1") (pinfunction "1_1") (pintype "bidirectional"))
      (node (ref "C51") (pin "1") (pinfunction "1_1") (pintype "bidirectional"))
      (node (ref "C52") (pin "1") (pinfunction "1_1") (pintype "bidirectional"))
      (node (ref "C55") (pin "1") (pinfunction "1_1") (pintype "bidirectional"))
      (node (ref "C57") (pin "1") (pinfunction "1_1") (pintype "bidirectional"))
      (node (ref "C59") (pin "1") (pinfunction "1_1") (pintype "bidirectional"))
      (node (ref "C61") (pin "1") (pinfunction "1_1") (pintype "bidirectional"))
      (node (ref "C62") (pin "2") (pinfunction "2_2") (pintype "bidirectional"))
      (node (ref "C64") (pin "1") (pinfunction "1_1") (pintype "bidirectional"))
      (node (ref "C65") (pin "1") (pinfunction "1_1") (pintype "bidirectional"))
      (node (ref "C66") (pin "1") (pinfunction "1_1") (pintype "bidirectional"))
      (node (ref "C69") (pin "1") (pinfunction "1_1") (pintype "bidirectional"))
      (node (ref "D2") (pin "1") (pinfunction "VDD_1") (pintype "bidirectional"))
      (node (ref "D3") (pin "1") (pinfunction "VDD_1") (pintype "bidirectional"))
      (node (ref "J4") (pin "1") (pinfunction "VCC_1") (pintype "bidirectional"))
      (node (ref "J5") (pin "1") (pinfunction "VCC_1") (pintype "bidirectional"))
      (node (ref "TP15") (pin "TP") (pinfunction "TP_TP") (pintype "input"))
      (node (ref "U1") (pin "15") (pinfunction "VDDLNA_15") (pintype "power_in"))
      (node (ref "U1") (pin "18") (pinfunction "VDDPA1_18") (pintype "power_in"))
      (node (ref "U1") (pin "19") (pinfunction "VDDPA2_19") (pintype "power_in"))
      (node (ref "U1") (pin "25") (pinfunction "VDDAON_25") (pintype "power_in"))
      (node (ref "U1") (pin "28") (pinfunction "VDDIOA_28") (pintype "power_in"))
      (node (ref "U1") (pin "47") (pinfunction "VDDBAT_47") (pintype "power_in"))
      (node (ref "U10") (pin "1") (pinfunction "VBAT_1") (pintype "power_in"))
      (node (ref "U10") (pin "24") (pinfunction "VDD/24_24") (pintype "power_in"))
      (node (ref "U10") (pin "36") (pinfunction "VDDIO2_36") (pintype "power_in"))
      (node (ref "U10") (pin "48") (pinfunction "VDD/48_48") (pintype "power_in"))
      (node (ref "U10") (pin "9") (pinfunction "VDDA_9") (pintype "power_in"))
      (node (ref "U3") (pin "10") (pinfunction "VDD_IO_10") (pintype "bidirectional"))
      (node (ref "U3") (pin "9") (pinfunction "VCC_9") (pintype "bidirectional"))
      (node (ref "U4") (pin "1") (pinfunction "VIN_1") (pintype "power_in"))
      (node (ref "U5") (pin "5") (pinfunction "OUT_5") (pintype "bidirectional"))
      (node (ref "U7") (pin "A22") (pinfunction "VDD_A22") (pintype "bidirectional"))
      (node (ref "U7") (pin "AD14") (pinfunction "VDD_AD14") (pintype "bidirectional"))
      (node (ref "U7") (pin "AD23") (pinfunction "VDD_AD23") (pintype "bidirectional"))
      (node (ref "U7") (pin "B1") (pinfunction "VDD_B1") (pintype "bidirectional"))
      (node (ref "U7") (pin "W1") (pinfunction "VDD_W1") (pintype "bidirectional"))
      (node (ref "U7") (pin "Y2") (pinfunction "VDDH_Y2") (pintype "bidirectional"))
      (node (ref "U8") (pin "5") (pinfunction "VSUPP_5") (pintype "bidirectional"))
      (node (ref "U8") (pin "6") (pinfunction "VSUPP_6") (pintype "bidirectional"))
    )
    (net (code "3") (name "ANT_SEL1") (class "Default")
      (node (ref "U10") (pin "27") (pinfunction "PB14_27") (pintype "bidirectional"))
      (node (ref "U9") (pin "3") (pinfunction "V1_3") (pintype "bidirectional"))
    )
    (net (code "4") (name "ANT_SEL2") (class "Default")
      (node (ref "U10") (pin "26") (pinfunction "PB13_26") (pintype "bidirectional"))
      (node (ref "U9") (pin "6") (pinfunction "V2_6") (pintype "bidirectional"))
    )
    (net (code "5") (name "ANT_SEL3") (class "Default")
      (node (ref "U10") (pin "25") (pinfunction "PB12_25") (pintype "bidirectional"))
      (node (ref "U9") (pin "7") (pinfunction "V3_7") (pintype "bidirectional"))
    )
    (net (code "6") (name "BATIN") (class "Default")
      (node (ref "C27") (pin "2") (pinfunction "2_2") (pintype "bidirectional"))
      (node (ref "R21") (pin "2") (pinfunction "2_2") (pintype "passive"))
      (node (ref "R22") (pin "1") (pinfunction "1_1") (pintype "passive"))
    )
    (net (code "7") (name "D+") (class "Default")
      (node (ref "J3") (pin "3") (pinfunction "D+_3") (pintype "bidirectional"))
      (node (ref "U2") (pin "14") (pinfunction "USBDP_14") (pintype "bidirectional"))
    )
    (net (code "8") (name "D-") (class "Default")
      (node (ref "J3") (pin "2") (pinfunction "D-_2") (pintype "bidirectional"))
      (node (ref "U2") (pin "15") (pinfunction "USBDM_15") (pintype "bidirectional"))
    )
    (net (code "9") (name "DBG_RX") (class "Default")
      (node (ref "R1") (pin "2") (pinfunction "2_2") (pintype "passive"))
      (node (ref "U7") (pin "M2") (pinfunction "P0.07_M2") (pintype "bidirectional"))
    )
    (net (code "10") (name "DBG_TX") (class "Default")
      (node (ref "R2") (pin "2") (pinfunction "2_2") (pintype "passive"))
      (node (ref "U7") (pin "T2") (pinfunction "P0.11_T2") (pintype "bidirectional"))
    )
    (net (code "11") (name "DW_IRQ") (class "Default")
      (node (ref "R20") (pin "2") (pinfunction "2_2") (pintype "passive"))
      (node (ref "U1") (pin "45") (pinfunction "IRQ/GPIO8_45") (pintype "bidirectional"))
      (node (ref "U10") (pin "20") (pinfunction "PB2_20") (pintype "bidirectional"))
    )
    (net (code "12") (name "DW_SPI_CLK") (class "Default")
      (node (ref "U1") (pin "41") (pinfunction "SPICLK_41") (pintype "input"))
      (node (ref "U10") (pin "15") (pinfunction "PA5_15") (pintype "bidirectional"))
    )
    (net (code "13") (name "DW_SPI_MISO") (class "Default")
      (node (ref "U1") (pin "40") (pinfunction "SPIMISO_40") (pintype "output"))
      (node (ref "U10") (pin "16") (pinfunction "PA6_16") (pintype "bidirectional"))
    )
    (net (code "14") (name "DW_SPI_MOSI") (class "Default")
      (node (ref "U1") (pin "39") (pinfunction "SPIMOSI_39") (pintype "input"))
      (node (ref "U10") (pin "17") (pinfunction "PA7_17") (pintype "bidirectional"))
    )
    (net (code "15") (name "DW_SYNC") (class "Default")
      (node (ref "U1") (pin "29") (pinfunction "SYNC/GPIO7_29") (pintype "bidirectional"))
    )
    (net (code "16") (name "DW_WAKEUP") (class "Default")
      (node (ref "U1") (pin "23") (pinfunction "WAKEUP_23") (pintype "input"))
      (node (ref "U10") (pin "19") (pinfunction "PB1_19") (pintype "bidirectional"))
    )
    (net (code "17") (name "EXT_I2C_SCL") (class "Default")
      (node (ref "TP1") (pin "TP") (pinfunction "TP_TP") (pintype "input"))
      (node (ref "U10") (pin "30") (pinfunction "PA9_30") (pintype "bidirectional"))
      (node (ref "U7") (pin "R1") (pinfunction "P1.09_R1") (pintype "bidirectional"))
    )
    (net (code "18") (name "EXT_I2C_SDA") (class "Default")
      (node (ref "TP2") (pin "TP") (pinfunction "TP_TP") (pintype "input"))
      (node (ref "U10") (pin "31") (pinfunction "PA10_31") (pintype "bidirectional"))
      (node (ref "U7") (pin "U1") (pinfunction "P0.12_U1") (pintype "bidirectional"))
    )
    (net (code "19") (name "GND") (class "Default")
      (node (ref "A4") (pin "S2") (pinfunction "GND_S2") (pintype "bidirectional"))
      (node (ref "C1") (pin "2") (pinfunction "2_2") (pintype "bidirectional"))
      (node (ref "C10") (pin "1") (pinfunction "1_1") (pintype "bidirectional"))
      (node (ref "C11") (pin "1") (pinfunction "1_1") (pintype "bidirectional"))
      (node (ref "C12") (pin "2") (pinfunction "2_2") (pintype "bidirectional"))
      (node (ref "C13") (pin "2") (pinfunction "2_2") (pintype "bidirectional"))
      (node (ref "C14") (pin "2") (pinfunction "2_2") (pintype "bidirectional"))
      (node (ref "C15") (pin "2") (pinfunction "2_2") (pintype "bidirectional"))
      (node (ref "C16") (pin "2") (pinfunction "2_2") (pintype "bidirectional"))
      (node (ref "C17") (pin "2") (pinfunction "2_2") (pintype "bidirectional"))
      (node (ref "C18") (pin "2") (pinfunction "2_2") (pintype "bidirectional"))
      (node (ref "C19") (pin "2") (pinfunction "2_2") (pintype "bidirectional"))
      (node (ref "C2") (pin "2") (pinfunction "2_2") (pintype "bidirectional"))
      (node (ref "C20") (pin "2") (pinfunction "2_2") (pintype "bidirectional"))
      (node (ref "C21") (pin "2") (pinfunction "2_2") (pintype "bidirectional"))
      (node (ref "C22") (pin "2") (pinfunction "2_2") (pintype "bidirectional"))
      (node (ref "C23") (pin "2") (pinfunction "2_2") (pintype "bidirectional"))
      (node (ref "C24") (pin "2") (pinfunction "2_2") (pintype "bidirectional"))
      (node (ref "C25") (pin "2") (pinfunction "2_2") (pintype "bidirectional"))
      (node (ref "C26") (pin "2") (pinfunction "2_2") (pintype "bidirectional"))
      (node (ref "C27") (pin "1") (pinfunction "1_1") (pintype "bidirectional"))
      (node (ref "C28") (pin "2") (pinfunction "2_2") (pintype "bidirectional"))
      (node (ref "C29") (pin "2") (pinfunction "2_2") (pintype "bidirectional"))
      (node (ref "C3") (pin "2") (pinfunction "2_2") (pintype "bidirectional"))
      (node (ref "C30") (pin "2") (pinfunction "2_2") (pintype "bidirectional"))
      (node (ref "C31") (pin "2") (pinfunction "2_2") (pintype "bidirectional"))
      (node (ref "C32") (pin "2") (pinfunction "2_2") (pintype "bidirectional"))
      (node (ref "C33") (pin "2") (pinfunction "2_2") (pintype "bidirectional"))
      (node (ref "C34") (pin "2") (pinfunction "2_2") (pintype "bidirectional"))
      (node (ref "C35") (pin "2") (pinfunction "2_2") (pintype "bidirectional"))
      (node (ref "C36") (pin "2") (pinfunction "2_2") (pintype "bidirectional"))
      (node (ref "C37") (pin "2") (pinfunction "2_2") (pintype "bidirectional"))
      (node (ref "C38") (pin "2") (pinfunction "2_2") (pintype "bidirectional"))
      (node (ref "C39") (pin "2") (pinfunction "2_2") (pintype "bidirectional"))
      (node (ref "C4") (pin "2") (pinfunction "2_2") (pintype "bidirectional"))
      (node (ref "C40") (pin "2") (pinfunction "2_2") (pintype "bidirectional"))
      (node (ref "C41") (pin "2") (pinfunction "2_2") (pintype "bidirectional"))
      (node (ref "C42") (pin "2") (pinfunction "2_2") (pintype "bidirectional"))
      (node (ref "C43") (pin "2") (pinfunction "2_2") (pintype "bidirectional"))
      (node (ref "C44") (pin "2") (pinfunction "2_2") (pintype "bidirectional"))
      (node (ref "C45") (pin "2") (pinfunction "2_2") (pintype "bidirectional"))
      (node (ref "C46") (pin "2") (pinfunction "2_2") (pintype "bidirectional"))
      (node (ref "C47") (pin "2") (pinfunction "2_2") (pintype "bidirectional"))
      (node (ref "C48") (pin "2") (pinfunction "2_2") (pintype "bidirectional"))
      (node (ref "C49") (pin "2") (pinfunction "2_2") (pintype "bidirectional"))
      (node (ref "C5") (pin "2") (pinfunction "2_2") (pintype "bidirectional"))
      (node (ref "C50") (pin "2") (pinfunction "2_2") (pintype "bidirectional"))
      (node (ref "C51") (pin "2") (pinfunction "2_2") (pintype "bidirectional"))
      (node (ref "C52") (pin "2") (pinfunction "2_2") (pintype "bidirectional"))
      (node (ref "C53") (pin "2") (pinfunction "2_2") (pintype "bidirectional"))
      (node (ref "C54") (pin "2") (pinfunction "2_2") (pintype "bidirectional"))
      (node (ref "C55") (pin "2") (pinfunction "2_2") (pintype "bidirectional"))
      (node (ref "C56") (pin "2") (pinfunction "2_2") (pintype "bidirectional"))
      (node (ref "C57") (pin "2") (pinfunction "2_2") (pintype "bidirectional"))
      (node (ref "C58") (pin "2") (pinfunction "2_2") (pintype "bidirectional"))
      (node (ref "C59") (pin "2") (pinfunction "2_2") (pintype "bidirectional"))
      (node (ref "C60") (pin "2") (pinfunction "2_2") (pintype "bidirectional"))
      (node (ref "C61") (pin "2") (pinfunction "2_2") (pintype "bidirectional"))
      (node (ref "C62") (pin "1") (pinfunction "1_1") (pintype "bidirectional"))
      (node (ref "C63") (pin "2") (pinfunction "2_2") (pintype "bidirectional"))
      (node (ref "C64") (pin "2") (pinfunction "2_2") (pintype "bidirectional"))
      (node (ref "C65") (pin "2") (pinfunction "2_2") (pintype "bidirectional"))
      (node (ref "C66") (pin "2") (pinfunction "2_2") (pintype "bidirectional"))
      (node (ref "C67") (pin "2") (pinfunction "2_2") (pintype "bidirectional"))
      (node (ref "C68") (pin "2") (pinfunction "2_2") (pintype "bidirectional"))
      (node (ref "C69") (pin "2") (pinfunction "2_2") (pintype "bidirectional"))
      (node (ref "C70") (pin "2") (pinfunction "2_2") (pintype "bidirectional"))
      (node (ref "C8") (pin "1") (pinfunction "1_1") (pintype "bidirectional"))
      (node (ref "C9") (pin "1") (pinfunction "1_1") (pintype "bidirectional"))
      (node (ref "J1") (pin "N") (pinfunction "-_N") (pintype "bidirectional"))
      (node (ref "J2") (pin "6") (pinfunction "GND_6") (pintype "bidirectional"))
      (node (ref "J2") (pin "B") (pinfunction "B_B") (pintype "bidirectional"))
      (node (ref "J2") (pin "MOUNT0") (pinfunction "GND_MOUNT0") (pintype "bidirectional"))
      (node (ref "J2") (pin "MOUNT1") (pinfunction "GND_MOUNT1") (pintype "bidirectional"))
      (node (ref "J2") (pin "MOUNT2") (pinfunction "GND_MOUNT2") (pintype "bidirectional"))
      (node (ref "J2") (pin "MOUNT3") (pinfunction "GND_MOUNT3") (pintype "bidirectional"))
      (node (ref "J3") (pin "5") (pinfunction "GND_5") (pintype "bidirectional"))
      (node (ref "J4") (pin "5") (pinfunction "GND_5") (pintype "bidirectional"))
      (node (ref "J5") (pin "5") (pinfunction "GND_5") (pintype "bidirectional"))
      (node (ref "R11") (pin "1") (pinfunction "1_1") (pintype "passive"))
      (node (ref "R15") (pin "1") (pinfunction "1_1") (pintype "passive"))
      (node (ref "R16") (pin "2") (pinfunction "2_2") (pintype "passive"))
      (node (ref "R18") (pin "2") (pinfunction "2_2") (pintype "passive"))
      (node (ref "R20") (pin "1") (pinfunction "1_1") (pintype "passive"))
      (node (ref "R21") (pin "1") (pinfunction "1_1") (pintype "passive"))
      (node (ref "T1") (pin "2") (pinfunction "GND_2") (pintype "power_in"))
      (node (ref "T1") (pin "5") (pinfunction "GND_5") (pintype "power_in"))
      (node (ref "TP10") (pin "P$1") (pinfunction "TESTPOINT_P$1") (pintype "bidirectional"))
      (node (ref "TP4") (pin "TP") (pinfunction "TP_TP") (pintype "input"))
      (node (ref "U1") (pin "22") (pinfunction "FORCEON_22") (pintype "input"))
      (node (ref "U1") (pin "32") (pinfunction "VSSIO/32_32") (pintype "bidirectional"))
      (node (ref "U1") (pin "43") (pinfunction "VSSIO/43_43") (pintype "bidirectional"))
      (node (ref "U1") (pin "46") (pinfunction "TESTMODE_46") (pintype "input"))
      (node (ref "U1") (pin "GND") (pinfunction "GND_GND") (pintype "power_in"))
      (node (ref "U10") (pin "23") (pinfunction "VSS/23_23") (pintype "power_in"))
      (node (ref "U10") (pin "35") (pinfunction "VSS/35_35") (pintype "power_in"))
      (node (ref "U10") (pin "47") (pinfunction "VSS/47_47") (pintype "power_in"))
      (node (ref "U10") (pin "8") (pinfunction "VSSA_8") (pintype "power_in"))
      (node (ref "U10") (pin "GND") (pinfunction "GND_GND") (pintype "power_in"))
      (node (ref "U2") (pin "17") (pinfunction "GND_17") (pintype "power_in"))
      (node (ref "U2") (pin "20") (pinfunction "GND_20") (pintype "power_in"))
      (node (ref "U2") (pin "24") (pinfunction "GND_24") (pintype "power_in"))
      (node (ref "U2") (pin "26") (pinfunction "TEST_26") (pintype "input"))
      (node (ref "U2") (pin "4") (pinfunction "GND_4") (pintype "power_in"))
      (node (ref "U3") (pin "5") (pinfunction "GND_5") (pintype "bidirectional"))
      (node (ref "U3") (pin "6") (pinfunction "GND_6") (pintype "bidirectional"))
      (node (ref "U3") (pin "7") (pinfunction "GND_7") (pintype "bidirectional"))
      (node (ref "U3") (pin "8") (pinfunction "GND_8") (pintype "bidirectional"))
      (node (ref "U4") (pin "4") (pinfunction "GND_4") (pintype "power_in"))
      (node (ref "U5") (pin "2") (pinfunction "GND_2") (pintype "bidirectional"))
      (node (ref "U6") (pin "6") (pinfunction "VSS_6") (pintype "power_in"))
      (node (ref "U6") (pin "GND") (pinfunction "GND_GND") (pintype "power_in"))
      (node (ref "U7") (pin "AD2") (pinfunction "VBUS_AD2") (pintype "bidirectional"))
      (node (ref "U7") (pin "B7") (pinfunction "VSS_B7") (pintype "bidirectional"))
      (node (ref "U7") (pin "F23") (pinfunction "VSS_PA_F23") (pintype "bidirectional"))
      (node (ref "U7") (pin "GND") (pinfunction "VSS_GND") (pintype "bidirectional"))
      (node (ref "U8") (pin "4") (pinfunction "GND_4") (pintype "bidirectional"))
      (node (ref "U9") (pin "GND") (pinfunction "GND_GND") (pintype "power_in"))
      (node (ref "X2") (pin "2") (pinfunction "GND_2") (pintype "bidirectional"))
      (node (ref "X2") (pin "4") (pinfunction "GND_4") (pintype "bidirectional"))
      (node (ref "X3") (pin "2") (pinfunction "GND_2") (pintype "bidirectional"))
      (node (ref "X3") (pin "4") (pinfunction "GND_4") (pintype "bidirectional"))
      (node (ref "X4") (pin "2") (pinfunction "GND_2") (pintype "bidirectional"))
      (node (ref "X4") (pin "4") (pinfunction "GND_4") (pintype "bidirectional"))
    )
    (net (code "20") (name "GPIO0") (class "Default")
      (node (ref "GPIO0") (pin "P$1") (pinfunction "TESTPOINT_P$1") (pintype "bidirectional"))
      (node (ref "U10") (pin "42") (pinfunction "PB6_42") (pintype "bidirectional"))
    )
    (net (code "21") (name "GPIO1") (class "Default")
      (node (ref "GPIO1") (pin "P$1") (pinfunction "TESTPOINT_P$1") (pintype "bidirectional"))
      (node (ref "U10") (pin "43") (pinfunction "PB7_43") (pintype "bidirectional"))
    )
    (net (code "22") (name "GPIO2") (class "Default")
      (node (ref "TP5") (pin "P$1") (pinfunction "TESTPOINT_P$1") (pintype "bidirectional"))
      (node (ref "U10") (pin "29") (pinfunction "PA8_29") (pintype "bidirectional"))
    )
    (net (code "23") (name "GPIO3") (class "Default")
      (node (ref "TP6") (pin "P$1") (pinfunction "TESTPOINT_P$1") (pintype "bidirectional"))
      (node (ref "U10") (pin "28") (pinfunction "PB15_28") (pintype "bidirectional"))
    )
    (net (code "24") (name "LED_BLUE") (class "Default")
      (node (ref "R10") (pin "2") (pinfunction "2_2") (pintype "passive"))
      (node (ref "U10") (pin "40") (pinfunction "PB4_40") (pintype "bidirectional"))
    )
    (net (code "25") (name "LED_GREEN") (class "Default")
      (node (ref "R9") (pin "2") (pinfunction "2_2") (pintype "passive"))
      (node (ref "U10") (pin "41") (pinfunction "PB5_41") (pintype "bidirectional"))
    )
    (net (code "26") (name "LED_NRF_BLUE") (class "Default")
      (node (ref "R6") (pin "2") (pinfunction "2_2") (pintype "passive"))
      (node (ref "U7") (pin "J1") (pinfunction "P0.04/AIN2_J1") (pintype "bidirectional"))
    )
    (net (code "27") (name "LED_NRF_GREEN") (class "Default")
      (node (ref "R5") (pin "2") (pinfunction "2_2") (pintype "passive"))
      (node (ref "U7") (pin "L1") (pinfunction "P0.06_L1") (pintype "bidirectional"))
    )
    (net (code "28") (name "LED_NRF_RED") (class "Default")
      (node (ref "R4") (pin "2") (pinfunction "2_2") (pintype "passive"))
      (node (ref "U7") (pin "K2") (pinfunction "P0.05/AIN3_K2") (pintype "bidirectional"))
    )
    (net (code "29") (name "LED_RED") (class "Default")
      (node (ref "R8") (pin "2") (pinfunction "2_2") (pintype "passive"))
      (node (ref "U10") (pin "39") (pinfunction "PB3_39") (pintype "bidirectional"))
    )
    (net (code "30") (name "NRF_GPIO_0") (class "Default")
      (node (ref "TP13") (pin "P$1") (pinfunction "TESTPOINT_P$1") (pintype "bidirectional"))
      (node (ref "U7") (pin "H2") (pinfunction "P0.27_H2") (pintype "bidirectional"))
    )
    (net (code "31") (name "NRF_GPIO_1") (class "Default")
      (node (ref "TP14") (pin "P$1") (pinfunction "TESTPOINT_P$1") (pintype "bidirectional"))
      (node (ref "U7") (pin "G1") (pinfunction "P0.26_G1") (pintype "bidirectional"))
    )
    (net (code "32") (name "NRF_IMU_INT1") (class "Default")
      (node (ref "U3") (pin "12") (pinfunction "INT1_12") (pintype "bidirectional"))
      (node (ref "U7") (pin "AD18") (pinfunction "P0.22_AD18") (pintype "bidirectional"))
    )
    (net (code "33") (name "NRF_IMU_INT2") (class "Default")
      (node (ref "U3") (pin "11") (pinfunction "INT2_11") (pintype "bidirectional"))
      (node (ref "U7") (pin "AD20") (pinfunction "P0.24_AD20") (pintype "bidirectional"))
    )
    (net (code "34") (name "NRF_MISO") (class "Default")
      (node (ref "J2") (pin "7") (pinfunction "DATA0/MISO_7") (pintype "bidirectional"))
      (node (ref "R14") (pin "1") (pinfunction "1_1") (pintype "passive"))
      (node (ref "U3") (pin "3") (pinfunction "MISO/SA0_3") (pintype "bidirectional"))
      (node (ref "U7") (pin "AD10") (pinfunction "P0.15_AD10") (pintype "bidirectional"))
    )
    (net (code "35") (name "NRF_MOSI") (class "Default")
      (node (ref "J2") (pin "3") (pinfunction "CMD/MOSI_3") (pintype "bidirectional"))
      (node (ref "R12") (pin "1") (pinfunction "1_1") (pintype "passive"))
      (node (ref "U3") (pin "4") (pinfunction "MOSI/SDA_4") (pintype "bidirectional"))
      (node (ref "U7") (pin "AD8") (pinfunction "P0.13_AD8") (pintype "bidirectional"))
    )
    (net (code "36") (name "NRF_SCK") (class "Default")
      (node (ref "J2") (pin "5") (pinfunction "CLK_5") (pintype "bidirectional"))
      (node (ref "U3") (pin "1") (pinfunction "SCL/SPC_1") (pintype "bidirectional"))
      (node (ref "U7") (pin "AD12") (pinfunction "P0.17_AD12") (pintype "bidirectional"))
    )
    (net (code "37") (name "NRF_SWDCLK") (class "Default")
      (node (ref "J4") (pin "4") (pinfunction "SWDCLK_4") (pintype "bidirectional"))
      (node (ref "U7") (pin "AA24") (pinfunction "SWDCLK_AA24") (pintype "bidirectional"))
    )
    (net (code "38") (name "NRF_SWDIO") (class "Default")
      (node (ref "J4") (pin "2") (pinfunction "SWDIO_2") (pintype "bidirectional"))
      (node (ref "U7") (pin "AC24") (pinfunction "SWDIO_AC24") (pintype "bidirectional"))
    )
    (net (code "39") (name "Net-(A4-ANTENNA)") (class "Default")
      (node (ref "A4") (pin "S1") (pinfunction "ANTENNA_S1") (pintype "bidirectional"))
      (node (ref "C2") (pin "1") (pinfunction "1_1") (pintype "bidirectional"))
      (node (ref "L1") (pin "1") (pinfunction "1_1") (pintype "bidirectional"))
    )
    (net (code "40") (name "Net-(C6-2)") (class "Default")
      (node (ref "C6") (pin "P$2") (pinfunction "2_P$2") (pintype "bidirectional"))
      (node (ref "T1") (pin "3") (pinfunction "BAL/3_3") (pintype "bidirectional"))
    )
    (net (code "41") (name "Net-(C7-2)") (class "Default")
      (node (ref "C7") (pin "P$2") (pinfunction "2_P$2") (pintype "bidirectional"))
      (node (ref "T1") (pin "4") (pinfunction "BAL/4_4") (pintype "bidirectional"))
    )
    (net (code "42") (name "Net-(C17-Pad1)") (class "Default")
      (node (ref "C17") (pin "1") (pinfunction "1_1") (pintype "bidirectional"))
      (node (ref "R17") (pin "2") (pinfunction "2_2") (pintype "passive"))
    )
    (net (code "43") (name "Net-(C22-Pad1)") (class "Default")
      (node (ref "C22") (pin "1") (pinfunction "1_1") (pintype "bidirectional"))
      (node (ref "R3") (pin "2") (pinfunction "2_2") (pintype "passive"))
    )
    (net (code "44") (name "Net-(D1-PadA)") (class "Default")
      (node (ref "D1") (pin "A") (pinfunction "A_A") (pintype "passive"))
      (node (ref "R7") (pin "1") (pinfunction "1_1") (pintype "passive"))
    )
    (net (code "45") (name "Net-(D2-B)") (class "Default")
      (node (ref "D2") (pin "3") (pinfunction "B_3") (pintype "output"))
      (node (ref "R6") (pin "1") (pinfunction "1_1") (pintype "passive"))
    )
    (net (code "46") (name "Net-(D2-G)") (class "Default")
      (node (ref "D2") (pin "4") (pinfunction "G_4") (pintype "output"))
      (node (ref "R5") (pin "1") (pinfunction "1_1") (pintype "passive"))
    )
    (net (code "47") (name "Net-(D2-R)") (class "Default")
      (node (ref "D2") (pin "2") (pinfunction "R_2") (pintype "output"))
      (node (ref "R4") (pin "1") (pinfunction "1_1") (pintype "passive"))
    )
    (net (code "48") (name "Net-(D3-B)") (class "Default")
      (node (ref "D3") (pin "3") (pinfunction "B_3") (pintype "output"))
      (node (ref "R10") (pin "1") (pinfunction "1_1") (pintype "passive"))
      (node (ref "TP9") (pin "P$1") (pinfunction "TESTPOINT_P$1") (pintype "bidirectional"))
    )
    (net (code "49") (name "Net-(D3-G)") (class "Default")
      (node (ref "D3") (pin "4") (pinfunction "G_4") (pintype "output"))
      (node (ref "R9") (pin "1") (pinfunction "1_1") (pintype "passive"))
      (node (ref "TP7") (pin "P$1") (pinfunction "TESTPOINT_P$1") (pintype "bidirectional"))
    )
    (net (code "50") (name "Net-(D3-R)") (class "Default")
      (node (ref "D3") (pin "2") (pinfunction "R_2") (pintype "output"))
      (node (ref "R8") (pin "1") (pinfunction "1_1") (pintype "passive"))
      (node (ref "TP8") (pin "P$1") (pinfunction "TESTPOINT_P$1") (pintype "bidirectional"))
    )
    (net (code "51") (name "Net-(J2-VCC)") (class "Default")
      (node (ref "C60") (pin "1") (pinfunction "1_1") (pintype "bidirectional"))
      (node (ref "J2") (pin "4") (pinfunction "VCC_4") (pintype "bidirectional"))
      (node (ref "R12") (pin "2") (pinfunction "2_2") (pintype "passive"))
      (node (ref "R13") (pin "2") (pinfunction "2_2") (pintype "passive"))
      (node (ref "R14") (pin "2") (pinfunction "2_2") (pintype "passive"))
      (node (ref "R19") (pin "2") (pinfunction "2_2") (pintype "passive"))
      (node (ref "U8") (pin "1") (pinfunction "VLOAD_1") (pintype "bidirectional"))
      (node (ref "U8") (pin "2") (pinfunction "VLOAD_2") (pintype "bidirectional"))
    )
    (net (code "52") (name "Net-(L2-Pad2)") (class "Default")
      (node (ref "L2") (pin "2") (pinfunction "2_2") (pintype "bidirectional"))
      (node (ref "L6") (pin "1") (pinfunction "1_1") (pintype "bidirectional"))
    )
    (net (code "53") (name "Net-(T1-UNB)") (class "Default")
      (node (ref "T1") (pin "1") (pinfunction "UNB_1") (pintype "bidirectional"))
      (node (ref "U9") (pin "1") (pinfunction "RFC_1") (pintype "bidirectional"))
    )
    (net (code "54") (name "Net-(TP11-TESTPOINT)") (class "Default")
      (node (ref "TP11") (pin "P$1") (pinfunction "TESTPOINT_P$1") (pintype "bidirectional"))
      (node (ref "U1") (pin "36") (pinfunction "GPIO2_36") (pintype "bidirectional"))
    )
    (net (code "55") (name "Net-(TP12-TESTPOINT)") (class "Default")
      (node (ref "TP12") (pin "P$1") (pinfunction "TESTPOINT_P$1") (pintype "bidirectional"))
      (node (ref "U1") (pin "35") (pinfunction "GPIO3_35") (pintype "bidirectional"))
    )
    (net (code "56") (name "Net-(U1-CLKTUNE)") (class "Default")
      (node (ref "C3") (pin "1") (pinfunction "1_1") (pintype "bidirectional"))
      (node (ref "R17") (pin "1") (pinfunction "1_1") (pintype "passive"))
      (node (ref "U1") (pin "8") (pinfunction "CLKTUNE_8") (pintype "bidirectional"))
    )
    (net (code "57") (name "Net-(U1-VCOTUNE)") (class "Default")
      (node (ref "C16") (pin "1") (pinfunction "1_1") (pintype "bidirectional"))
      (node (ref "R3") (pin "1") (pinfunction "1_1") (pintype "passive"))
      (node (ref "U1") (pin "12") (pinfunction "VCOTUNE_12") (pintype "bidirectional"))
    )
    (net (code "58") (name "Net-(U1-VREF)") (class "Default")
      (node (ref "R15") (pin "2") (pinfunction "2_2") (pintype "passive"))
      (node (ref "U1") (pin "5") (pinfunction "VREF_5") (pintype "bidirectional"))
    )
    (net (code "59") (name "Net-(U2-3V3OUT)") (class "Default")
      (node (ref "C28") (pin "1") (pinfunction "1_1") (pintype "bidirectional"))
      (node (ref "U2") (pin "1") (pinfunction "VCCIO_1") (pintype "power_in"))
      (node (ref "U2") (pin "16") (pinfunction "3V3OUT_16") (pintype "output"))
    )
    (net (code "60") (name "Net-(U2-RXD)") (class "Default")
      (node (ref "R2") (pin "1") (pinfunction "1_1") (pintype "passive"))
      (node (ref "U2") (pin "2") (pinfunction "RXD_2") (pintype "input"))
    )
    (net (code "61") (name "Net-(U2-TXD)") (class "Default")
      (node (ref "R1") (pin "1") (pinfunction "1_1") (pintype "passive"))
      (node (ref "U2") (pin "30") (pinfunction "TXD_30") (pintype "output"))
    )
    (net (code "62") (name "Net-(U5-BP)") (class "Default")
      (node (ref "C23") (pin "1") (pinfunction "1_1") (pintype "bidirectional"))
      (node (ref "U5") (pin "4") (pinfunction "BP_4") (pintype "bidirectional"))
    )
    (net (code "63") (name "Net-(U6-PROG)") (class "Default")
      (node (ref "R11") (pin "2") (pinfunction "2_2") (pintype "passive"))
      (node (ref "U6") (pin "8") (pinfunction "PROG_8") (pintype "bidirectional"))
    )
    (net (code "64") (name "Net-(U6-STAT)") (class "Default")
      (node (ref "D1") (pin "C") (pinfunction "C_C") (pintype "passive"))
      (node (ref "U6") (pin "5") (pinfunction "STAT_5") (pintype "bidirectional"))
    )
    (net (code "65") (name "Net-(U7-ANT)") (class "Default")
      (node (ref "C1") (pin "1") (pinfunction "1_1") (pintype "bidirectional"))
      (node (ref "L1") (pin "2") (pinfunction "2_2") (pintype "bidirectional"))
      (node (ref "U7") (pin "H23") (pinfunction "ANT_H23") (pintype "bidirectional"))
    )
    (net (code "66") (name "Net-(U7-DCC)") (class "Default")
      (node (ref "L6") (pin "2") (pinfunction "2_2") (pintype "bidirectional"))
      (node (ref "U7") (pin "B3") (pinfunction "DCC_B3") (pintype "bidirectional"))
    )
    (net (code "67") (name "Net-(U7-DEC1)") (class "Default")
      (node (ref "C32") (pin "1") (pinfunction "1_1") (pintype "bidirectional"))
      (node (ref "U7") (pin "C1") (pinfunction "DEC1_C1") (pintype "bidirectional"))
    )
    (net (code "68") (name "Net-(U7-DEC3)") (class "Default")
      (node (ref "C18") (pin "1") (pinfunction "1_1") (pintype "bidirectional"))
      (node (ref "U7") (pin "D23") (pinfunction "DEC3_D23") (pintype "bidirectional"))
    )
    (net (code "69") (name "Net-(U7-DEC4)") (class "Default")
      (node (ref "C26") (pin "1") (pinfunction "1_1") (pintype "bidirectional"))
      (node (ref "C56") (pin "1") (pinfunction "1_1") (pintype "bidirectional"))
      (node (ref "L2") (pin "1") (pinfunction "1_1") (pintype "bidirectional"))
      (node (ref "U7") (pin "B5") (pinfunction "DEC4_B5") (pintype "bidirectional"))
      (node (ref "U7") (pin "E24") (pinfunction "DEC6_E24") (pintype "bidirectional"))
    )
    (net (code "70") (name "Net-(U7-DEC5)") (class "Default")
      (node (ref "C21") (pin "1") (pinfunction "1_1") (pintype "bidirectional"))
      (node (ref "U7") (pin "N24") (pinfunction "DEC5_N24") (pintype "bidirectional"))
    )
    (net (code "71") (name "Net-(U7-XC1)") (class "Default")
      (node (ref "C8") (pin "2") (pinfunction "2_2") (pintype "bidirectional"))
      (node (ref "U7") (pin "B24") (pinfunction "XC1_B24") (pintype "bidirectional"))
      (node (ref "X3") (pin "3") (pinfunction "2_3") (pintype "bidirectional"))
    )
    (net (code "72") (name "Net-(U7-XC2)") (class "Default")
      (node (ref "C9") (pin "2") (pinfunction "2_2") (pintype "bidirectional"))
      (node (ref "U7") (pin "A23") (pinfunction "XC2_A23") (pintype "bidirectional"))
      (node (ref "X3") (pin "1") (pinfunction "1_1") (pintype "bidirectional"))
    )
    (net (code "73") (name "Net-(U10-PF11-BOOT0)") (class "Default")
      (node (ref "R16") (pin "1") (pinfunction "1_1") (pintype "passive"))
      (node (ref "U10") (pin "44") (pinfunction "PF11-BOOT0_44") (pintype "bidirectional"))
    )
    (net (code "74") (name "OSC_IN") (class "Default")
      (node (ref "C14") (pin "1") (pinfunction "1_1") (pintype "bidirectional"))
      (node (ref "U10") (pin "5") (pinfunction "PF0-OSC_IN_5") (pintype "bidirectional"))
      (node (ref "X2") (pin "1") (pinfunction "1_1") (pintype "bidirectional"))
    )
    (net (code "75") (name "OSC_OUT") (class "Default")
      (node (ref "C15") (pin "1") (pinfunction "1_1") (pintype "bidirectional"))
      (node (ref "U10") (pin "6") (pinfunction "PF1-OSC_OUT_6") (pintype "bidirectional"))
      (node (ref "X2") (pin "3") (pinfunction "2_3") (pintype "bidirectional"))
    )
    (net (code "76") (name "REG_EN") (class "Default")
      (node (ref "U1") (pin "21") (pinfunction "EXTON_21") (pintype "output"))
      (node (ref "U4") (pin "2") (pinfunction "EN_2") (pintype "bidirectional"))
    )
    (net (code "77") (name "RF1") (class "Default")
      (node (ref "A1") (pin "A") (pinfunction "ANTENNA_A") (pintype "bidirectional"))
      (node (ref "U9") (pin "4") (pinfunction "RF1_4") (pintype "bidirectional"))
    )
    (net (code "78") (name "RF2") (class "Default")
      (node (ref "A2") (pin "A") (pinfunction "ANTENNA_A") (pintype "bidirectional"))
      (node (ref "U9") (pin "5") (pinfunction "RF2_5") (pintype "bidirectional"))
    )
    (net (code "79") (name "RF3") (class "Default")
      (node (ref "A3") (pin "A") (pinfunction "ANTENNA_A") (pintype "bidirectional"))
      (node (ref "U9") (pin "8") (pinfunction "RF3_8") (pintype "bidirectional"))
    )
    (net (code "80") (name "RF_N") (class "Default")
      (node (ref "C6") (pin "P$1") (pinfunction "1_P$1") (pintype "bidirectional"))
      (node (ref "U1") (pin "17") (pinfunction "RF_N_17") (pintype "bidirectional"))
    )
    (net (code "81") (name "RF_P") (class "Default")
      (node (ref "C7") (pin "P$1") (pinfunction "1_P$1") (pintype "bidirectional"))
      (node (ref "U1") (pin "16") (pinfunction "RF_P_16") (pintype "bidirectional"))
    )
    (net (code "82") (name "SD_EN") (class "Default")
      (node (ref "R18") (pin "1") (pinfunction "1_1") (pintype "passive"))
      (node (ref "U7") (pin "AC9") (pinfunction "P0.14_AC9") (pintype "bidirectional"))
      (node (ref "U8") (pin "3") (pinfunction "EN_3") (pintype "bidirectional"))
    )
    (net (code "83") (name "STM_INTERRUPT") (class "Default")
      (node (ref "TP3") (pin "TP") (pinfunction "TP_TP") (pintype "input"))
      (node (ref "U10") (pin "12") (pinfunction "PA2_12") (pintype "bidirectional"))
      (node (ref "U7") (pin "N1") (pinfunction "P0.08_N1") (pintype "bidirectional"))
    )
    (net (code "84") (name "STM_SWCLK") (class "Default")
      (node (ref "J5") (pin "4") (pinfunction "SWDCLK_4") (pintype "bidirectional"))
      (node (ref "U10") (pin "37") (pinfunction "PA14_37") (pintype "bidirectional"))
    )
    (net (code "85") (name "STM_SWDIO") (class "Default")
      (node (ref "J5") (pin "2") (pinfunction "SWDIO_2") (pintype "bidirectional"))
      (node (ref "U10") (pin "34") (pinfunction "PA13_34") (pintype "bidirectional"))
    )
    (net (code "86") (name "VBAT") (class "Default")
      (node (ref "C58") (pin "1") (pinfunction "1_1") (pintype "bidirectional"))
      (node (ref "C68") (pin "1") (pinfunction "1_1") (pintype "bidirectional"))
      (node (ref "J1") (pin "P") (pinfunction "+_P") (pintype "bidirectional"))
      (node (ref "R22") (pin "2") (pinfunction "2_2") (pintype "passive"))
      (node (ref "U5") (pin "1") (pinfunction "IN_1") (pintype "bidirectional"))
      (node (ref "U5") (pin "3") (pinfunction "~{SHDN}_3") (pintype "bidirectional"))
      (node (ref "U6") (pin "3") (pinfunction "VBAT/3_3") (pintype "power_in"))
      (node (ref "U6") (pin "4") (pinfunction "VBAT/4_4") (pintype "power_in"))
    )
    (net (code "87") (name "VDDCLK") (class "Default")
      (node (ref "C39") (pin "1") (pinfunction "1_1") (pintype "bidirectional"))
      (node (ref "U1") (pin "9") (pinfunction "VDDCLK_9") (pintype "power_in"))
    )
    (net (code "88") (name "VDDDIG") (class "Default")
      (node (ref "C35") (pin "1") (pinfunction "1_1") (pintype "bidirectional"))
      (node (ref "C36") (pin "1") (pinfunction "1_1") (pintype "bidirectional"))
      (node (ref "U1") (pin "20") (pinfunction "VDDREG_20") (pintype "power_in"))
      (node (ref "U1") (pin "44") (pinfunction "VDDDIG_44") (pintype "power_in"))
    )
    (net (code "89") (name "VDDIF") (class "Default")
      (node (ref "C42") (pin "1") (pinfunction "1_1") (pintype "bidirectional"))
      (node (ref "U1") (pin "7") (pinfunction "VDDIF_7") (pintype "power_in"))
    )
    (net (code "90") (name "VDDIO") (class "Default")
      (node (ref "C41") (pin "1") (pinfunction "1_1") (pintype "bidirectional"))
      (node (ref "C53") (pin "1") (pinfunction "1_1") (pintype "bidirectional"))
      (node (ref "U1") (pin "31") (pinfunction "VDDIO/31_31") (pintype "power_in"))
      (node (ref "U1") (pin "42") (pinfunction "VDDIO/42_42") (pintype "power_in"))
    )
    (net (code "91") (name "VDDMS") (class "Default")
      (node (ref "C38") (pin "1") (pinfunction "1_1") (pintype "bidirectional"))
      (node (ref "U1") (pin "6") (pinfunction "VDDMS_6") (pintype "power_in"))
    )
    (net (code "92") (name "VDDSYN") (class "Default")
      (node (ref "C40") (pin "1") (pinfunction "1_1") (pintype "bidirectional"))
      (node (ref "U1") (pin "10") (pinfunction "VDDSYN_10") (pintype "power_in"))
    )
    (net (code "93") (name "VDDVCO") (class "Default")
      (node (ref "C43") (pin "1") (pinfunction "1_1") (pintype "bidirectional"))
      (node (ref "U1") (pin "11") (pinfunction "VDDVCO_11") (pintype "power_in"))
    )
    (net (code "94") (name "VUSB") (class "Default")
      (node (ref "C54") (pin "1") (pinfunction "1_1") (pintype "bidirectional"))
      (node (ref "C67") (pin "1") (pinfunction "1_1") (pintype "bidirectional"))
      (node (ref "J3") (pin "1") (pinfunction "+5V_1") (pintype "bidirectional"))
      (node (ref "R7") (pin "2") (pinfunction "2_2") (pintype "passive"))
      (node (ref "U2") (pin "19") (pinfunction "VCC_19") (pintype "power_in"))
      (node (ref "U6") (pin "1") (pinfunction "VDD/1_1") (pintype "power_in"))
      (node (ref "U6") (pin "2") (pinfunction "VDD/2_2") (pintype "power_in"))
    )
    (net (code "95") (name "XL3") (class "Default")
      (node (ref "C11") (pin "2") (pinfunction "2_2") (pintype "bidirectional"))
      (node (ref "U7") (pin "D2") (pinfunction "P0.00/XL1_D2") (pintype "bidirectional"))
      (node (ref "X1") (pin "A") (pinfunction "1_A") (pintype "bidirectional"))
    )
    (net (code "96") (name "XL4") (class "Default")
      (node (ref "C10") (pin "2") (pinfunction "2_2") (pintype "bidirectional"))
      (node (ref "U7") (pin "F2") (pinfunction "P0.01/XL2_F2") (pintype "bidirectional"))
      (node (ref "X1") (pin "B") (pinfunction "2_B") (pintype "bidirectional"))
    )
    (net (code "97") (name "XTAL1") (class "Default")
      (node (ref "C13") (pin "1") (pinfunction "1_1") (pintype "bidirectional"))
      (node (ref "U1") (pin "3") (pinfunction "XTAL1_3") (pintype "input"))
      (node (ref "X4") (pin "3") (pinfunction "2_3") (pintype "bidirectional"))
    )
    (net (code "98") (name "XTAL2") (class "Default")
      (node (ref "C12") (pin "1") (pinfunction "1_1") (pintype "bidirectional"))
      (node (ref "U1") (pin "4") (pinfunction "XTAL2_4") (pintype "input"))
      (node (ref "X4") (pin "1") (pinfunction "1_1") (pintype "bidirectional"))
    )
    (net (code "99") (name "unconnected-(J2-DATA1{slash}RSV-Pad8)") (class "Default")
      (node (ref "J2") (pin "8") (pinfunction "DATA1/RSV_8") (pintype "bidirectional"))
    )
    (net (code "100") (name "unconnected-(J2-DATA2{slash}NC-Pad1)") (class "Default")
      (node (ref "J2") (pin "1") (pinfunction "DATA2/NC_1") (pintype "bidirectional"))
    )
    (net (code "101") (name "unconnected-(J3-ID-Pad4)") (class "Default")
      (node (ref "J3") (pin "4") (pinfunction "ID_4") (pintype "bidirectional"))
    )
    (net (code "102") (name "unconnected-(J4-SWO-Pad6)") (class "Default")
      (node (ref "J4") (pin "6") (pinfunction "SWO_6") (pintype "bidirectional"))
    )
    (net (code "103") (name "unconnected-(J4-~{RESET}-Pad3)") (class "Default")
      (node (ref "J4") (pin "3") (pinfunction "~{RESET}_3") (pintype "bidirectional"))
    )
    (net (code "104") (name "unconnected-(J5-SWO-Pad6)") (class "Default")
      (node (ref "J5") (pin "6") (pinfunction "SWO_6") (pintype "bidirectional"))
    )
    (net (code "105") (name "unconnected-(U1-GPIO0-Pad38)") (class "Default")
      (node (ref "U1") (pin "38") (pinfunction "GPIO0_38") (pintype "bidirectional"))
    )
    (net (code "106") (name "unconnected-(U1-GPIO1-Pad37)") (class "Default")
      (node (ref "U1") (pin "37") (pinfunction "GPIO1_37") (pintype "bidirectional"))
    )
    (net (code "107") (name "unconnected-(U1-GPIO4-Pad34)") (class "Default")
      (node (ref "U1") (pin "34") (pinfunction "GPIO4_34") (pintype "bidirectional"))
    )
    (net (code "108") (name "unconnected-(U1-GPIO5-Pad33)") (class "Default")
      (node (ref "U1") (pin "33") (pinfunction "GPIO5_33") (pintype "bidirectional"))
    )
    (net (code "109") (name "unconnected-(U1-GPIO6-Pad30)") (class "Default")
      (node (ref "U1") (pin "30") (pinfunction "GPIO6_30") (pintype "bidirectional"))
    )
    (net (code "110") (name "unconnected-(U2-CBUS0-Pad22)") (class "Default")
      (node (ref "U2") (pin "22") (pinfunction "CBUS0_22") (pintype "bidirectional"))
    )
    (net (code "111") (name "unconnected-(U2-CBUS1-Pad21)") (class "Default")
      (node (ref "U2") (pin "21") (pinfunction "CBUS1_21") (pintype "bidirectional"))
    )
    (net (code "112") (name "unconnected-(U2-CBUS2-Pad10)") (class "Default")
      (node (ref "U2") (pin "10") (pinfunction "CBUS2_10") (pintype "bidirectional"))
    )
    (net (code "113") (name "unconnected-(U2-CBUS3-Pad11)") (class "Default")
      (node (ref "U2") (pin "11") (pinfunction "CBUS3_11") (pintype "bidirectional"))
    )
    (net (code "114") (name "unconnected-(U2-CBUS4-Pad9)") (class "Default")
      (node (ref "U2") (pin "9") (pinfunction "CBUS4_9") (pintype "bidirectional"))
    )
    (net (code "115") (name "unconnected-(U2-OSCI-Pad27)") (class "Default")
      (node (ref "U2") (pin "27") (pinfunction "OSCI_27") (pintype "input"))
    )
    (net (code "116") (name "unconnected-(U2-OSCO-Pad28)") (class "Default")
      (node (ref "U2") (pin "28") (pinfunction "OSCO_28") (pintype "output"))
    )
    (net (code "117") (name "unconnected-(U2-~{CTS}-Pad8)") (class "Default")
      (node (ref "U2") (pin "8") (pinfunction "~{CTS}_8") (pintype "input"))
    )
    (net (code "118") (name "unconnected-(U2-~{DCD}-Pad7)") (class "Default")
      (node (ref "U2") (pin "7") (pinfunction "~{DCD}_7") (pintype "input"))
    )
    (net (code "119") (name "unconnected-(U2-~{DSR}-Pad6)") (class "Default")
      (node (ref "U2") (pin "6") (pinfunction "~{DSR}_6") (pintype "input"))
    )
    (net (code "120") (name "unconnected-(U2-~{DTR}-Pad31)") (class "Default")
      (node (ref "U2") (pin "31") (pinfunction "~{DTR}_31") (pintype "output"))
    )
    (net (code "121") (name "unconnected-(U2-~{RI}-Pad3)") (class "Default")
      (node (ref "U2") (pin "3") (pinfunction "~{RI}_3") (pintype "input"))
    )
    (net (code "122") (name "unconnected-(U2-~{RTS}-Pad32)") (class "Default")
      (node (ref "U2") (pin "32") (pinfunction "~{RTS}_32") (pintype "output"))
    )
    (net (code "123") (name "unconnected-(U6-NC-Pad7)") (class "Default")
      (node (ref "U6") (pin "7") (pinfunction "NC_7") (pintype "no_connect"))
    )
    (net (code "124") (name "unconnected-(U7-D+-PadAD6)") (class "Default")
      (node (ref "U7") (pin "AD6") (pinfunction "D+_AD6") (pintype "bidirectional"))
    )
    (net (code "125") (name "unconnected-(U7-D--PadAD4)") (class "Default")
      (node (ref "U7") (pin "AD4") (pinfunction "D-_AD4") (pintype "bidirectional"))
    )
    (net (code "126") (name "unconnected-(U7-DCCH-PadAB2)") (class "Default")
      (node (ref "U7") (pin "AB2") (pinfunction "DCCH_AB2") (pintype "bidirectional"))
    )
    (net (code "127") (name "unconnected-(U7-DEC2-PadA18)") (class "Default")
      (node (ref "U7") (pin "A18") (pinfunction "DEC2_A18") (pintype "bidirectional"))
    )
    (net (code "128") (name "unconnected-(U7-DECUSB-PadAC5)") (class "Default")
      (node (ref "U7") (pin "AC5") (pinfunction "DECUSB_AC5") (pintype "bidirectional"))
    )
    (net (code "129") (name "unconnected-(U7-P0.02{slash}AIN0-PadA12)") (class "Default")
      (node (ref "U7") (pin "A12") (pinfunction "P0.02/AIN0_A12") (pintype "bidirectional"))
    )
    (net (code "130") (name "unconnected-(U7-P0.03{slash}AIN1-PadB13)") (class "Default")
      (node (ref "U7") (pin "B13") (pinfunction "P0.03/AIN1_B13") (pintype "bidirectional"))
    )
    (net (code "131") (name "unconnected-(U7-P0.09{slash}NFC1-PadL24)") (class "Default")
      (node (ref "U7") (pin "L24") (pinfunction "P0.09/NFC1_L24") (pintype "bidirectional"))
    )
    (net (code "132") (name "unconnected-(U7-P0.10{slash}NFC2-PadJ24)") (class "Default")
      (node (ref "U7") (pin "J24") (pinfunction "P0.10/NFC2_J24") (pintype "bidirectional"))
    )
    (net (code "133") (name "unconnected-(U7-P0.19-PadAC15)") (class "Default")
      (node (ref "U7") (pin "AC15") (pinfunction "P0.19_AC15") (pintype "bidirectional"))
    )
    (net (code "134") (name "unconnected-(U7-P0.20-PadAD16)") (class "Default")
      (node (ref "U7") (pin "AD16") (pinfunction "P0.20_AD16") (pintype "bidirectional"))
    )
    (net (code "135") (name "unconnected-(U7-P0.21-PadAC17)") (class "Default")
      (node (ref "U7") (pin "AC17") (pinfunction "P0.21_AC17") (pintype "bidirectional"))
    )
    (net (code "136") (name "unconnected-(U7-P0.23-PadAC19)") (class "Default")
      (node (ref "U7") (pin "AC19") (pinfunction "P0.23_AC19") (pintype "bidirectional"))
    )
    (net (code "137") (name "unconnected-(U7-P0.25-PadAC21)") (class "Default")
      (node (ref "U7") (pin "AC21") (pinfunction "P0.25_AC21") (pintype "bidirectional"))
    )
    (net (code "138") (name "unconnected-(U7-P0.28{slash}AIN4-PadB11)") (class "Default")
      (node (ref "U7") (pin "B11") (pinfunction "P0.28/AIN4_B11") (pintype "bidirectional"))
    )
    (net (code "139") (name "unconnected-(U7-P0.29{slash}AIN5-PadA10)") (class "Default")
      (node (ref "U7") (pin "A10") (pinfunction "P0.29/AIN5_A10") (pintype "bidirectional"))
    )
    (net (code "140") (name "unconnected-(U7-P0.30{slash}AIN6-PadB9)") (class "Default")
      (node (ref "U7") (pin "B9") (pinfunction "P0.30/AIN6_B9") (pintype "bidirectional"))
    )
    (net (code "141") (name "unconnected-(U7-P0.31{slash}AIN7-PadA8)") (class "Default")
      (node (ref "U7") (pin "A8") (pinfunction "P0.31/AIN7_A8") (pintype "bidirectional"))
    )
    (net (code "142") (name "unconnected-(U7-P1.01-PadY23)") (class "Default")
      (node (ref "U7") (pin "Y23") (pinfunction "P1.01_Y23") (pintype "bidirectional"))
    )
    (net (code "143") (name "unconnected-(U7-P1.02-PadW24)") (class "Default")
      (node (ref "U7") (pin "W24") (pinfunction "P1.02_W24") (pintype "bidirectional"))
    )
    (net (code "144") (name "unconnected-(U7-P1.03-PadV23)") (class "Default")
      (node (ref "U7") (pin "V23") (pinfunction "P1.03_V23") (pintype "bidirectional"))
    )
    (net (code "145") (name "unconnected-(U7-P1.04-PadU24)") (class "Default")
      (node (ref "U7") (pin "U24") (pinfunction "P1.04_U24") (pintype "bidirectional"))
    )
    (net (code "146") (name "unconnected-(U7-P1.05-PadT23)") (class "Default")
      (node (ref "U7") (pin "T23") (pinfunction "P1.05_T23") (pintype "bidirectional"))
    )
    (net (code "147") (name "unconnected-(U7-P1.06-PadR24)") (class "Default")
      (node (ref "U7") (pin "R24") (pinfunction "P1.06_R24") (pintype "bidirectional"))
    )
    (net (code "148") (name "unconnected-(U7-P1.07-PadP23)") (class "Default")
      (node (ref "U7") (pin "P23") (pinfunction "P1.07_P23") (pintype "bidirectional"))
    )
    (net (code "149") (name "unconnected-(U7-P1.10-PadA20)") (class "Default")
      (node (ref "U7") (pin "A20") (pinfunction "P1.10_A20") (pintype "bidirectional"))
    )
    (net (code "150") (name "unconnected-(U7-P1.11-PadB19)") (class "Default")
      (node (ref "U7") (pin "B19") (pinfunction "P1.11_B19") (pintype "bidirectional"))
    )
    (net (code "151") (name "unconnected-(U7-P1.12-PadB17)") (class "Default")
      (node (ref "U7") (pin "B17") (pinfunction "P1.12_B17") (pintype "bidirectional"))
    )
    (net (code "152") (name "unconnected-(U7-P1.13-PadA16)") (class "Default")
      (node (ref "U7") (pin "A16") (pinfunction "P1.13_A16") (pintype "bidirectional"))
    )
    (net (code "153") (name "unconnected-(U7-P1.14-PadB15)") (class "Default")
      (node (ref "U7") (pin "B15") (pinfunction "P1.14_B15") (pintype "bidirectional"))
    )
    (net (code "154") (name "unconnected-(U7-P1.15-PadA14)") (class "Default")
      (node (ref "U7") (pin "A14") (pinfunction "P1.15_A14") (pintype "bidirectional"))
    )
    (net (code "155") (name "unconnected-(U10-PA0-Pad10)") (class "Default")
      (node (ref "U10") (pin "10") (pinfunction "PA0_10") (pintype "bidirectional"))
    )
    (net (code "156") (name "unconnected-(U10-PA1-Pad11)") (class "Default")
      (node (ref "U10") (pin "11") (pinfunction "PA1_11") (pintype "bidirectional"))
    )
    (net (code "157") (name "unconnected-(U10-PA3-Pad13)") (class "Default")
      (node (ref "U10") (pin "13") (pinfunction "PA3_13") (pintype "bidirectional"))
    )
    (net (code "158") (name "unconnected-(U10-PA11-Pad32)") (class "Default")
      (node (ref "U10") (pin "32") (pinfunction "PA11_32") (pintype "bidirectional"))
    )
    (net (code "159") (name "unconnected-(U10-PA12-Pad33)") (class "Default")
      (node (ref "U10") (pin "33") (pinfunction "PA12_33") (pintype "bidirectional"))
    )
    (net (code "160") (name "unconnected-(U10-PA15-Pad38)") (class "Default")
      (node (ref "U10") (pin "38") (pinfunction "PA15_38") (pintype "bidirectional"))
    )
    (net (code "161") (name "unconnected-(U10-PB8-Pad45)") (class "Default")
      (node (ref "U10") (pin "45") (pinfunction "PB8_45") (pintype "bidirectional"))
    )
    (net (code "162") (name "unconnected-(U10-PB9-Pad46)") (class "Default")
      (node (ref "U10") (pin "46") (pinfunction "PB9_46") (pintype "bidirectional"))
    )
    (net (code "163") (name "unconnected-(U10-PB10-Pad21)") (class "Default")
      (node (ref "U10") (pin "21") (pinfunction "PB10_21") (pintype "bidirectional"))
    )
    (net (code "164") (name "unconnected-(U10-PB11-Pad22)") (class "Default")
      (node (ref "U10") (pin "22") (pinfunction "PB11_22") (pintype "bidirectional"))
    )
    (net (code "165") (name "unconnected-(U10-PC13-Pad2)") (class "Default")
      (node (ref "U10") (pin "2") (pinfunction "PC13_2") (pintype "bidirectional"))
    )
    (net (code "166") (name "unconnected-(U10-PC14-OSC32_IN-Pad3)") (class "Default")
      (node (ref "U10") (pin "3") (pinfunction "PC14-OSC32_IN_3") (pintype "bidirectional"))
    )
    (net (code "167") (name "unconnected-(U10-PC15-OSC32_OUT-Pad4)") (class "Default")
      (node (ref "U10") (pin "4") (pinfunction "PC15-OSC32_OUT_4") (pintype "bidirectional"))
    )
    (net (code "168") (name "~{DW_RST}") (class "Default")
      (node (ref "U1") (pin "27") (pinfunction "~{RST}_27") (pintype "bidirectional"))
      (node (ref "U10") (pin "18") (pinfunction "PB0_18") (pintype "bidirectional"))
    )
    (net (code "169") (name "~{DW_SPI_CS}") (class "Default")
      (node (ref "U1") (pin "24") (pinfunction "~{SPICS}_24") (pintype "input"))
      (node (ref "U10") (pin "14") (pinfunction "PA4_14") (pintype "bidirectional"))
    )
    (net (code "170") (name "~{FT_RST}") (class "Default")
      (node (ref "U2") (pin "18") (pinfunction "~{RESET}_18") (pintype "input"))
      (node (ref "U7") (pin "P2") (pinfunction "P1.08_P2") (pintype "bidirectional"))
    )
    (net (code "171") (name "~{NRF_CS_IMU}") (class "Default")
      (node (ref "U3") (pin "2") (pinfunction "CS_2") (pintype "bidirectional"))
      (node (ref "U7") (pin "AC11") (pinfunction "P0.16_AC11") (pintype "bidirectional"))
    )
    (net (code "172") (name "~{NRF_CS_SD}") (class "Default")
      (node (ref "J2") (pin "2") (pinfunction "DATA3-CD/CS_N_2") (pintype "bidirectional"))
      (node (ref "R13") (pin "1") (pinfunction "1_1") (pintype "passive"))
      (node (ref "U7") (pin "AC13") (pinfunction "P0.18_AC13") (pintype "bidirectional"))
    )
    (net (code "173") (name "~{SD_DETECT}") (class "Default")
      (node (ref "J2") (pin "A") (pinfunction "A_A") (pintype "bidirectional"))
      (node (ref "R19") (pin "1") (pinfunction "1_1") (pintype "passive"))
      (node (ref "U7") (pin "AD22") (pinfunction "P1.00_AD22") (pintype "bidirectional"))
    )
    (net (code "174") (name "~{STM_RST}") (class "Default")
      (node (ref "J5") (pin "3") (pinfunction "~{RESET}_3") (pintype "bidirectional"))
      (node (ref "U10") (pin "7") (pinfunction "~{RST}_7") (pintype "bidirectional"))
    )
  )
)
